# FP6120.net
KiCad netlist of a schematic drawn in EAGLE
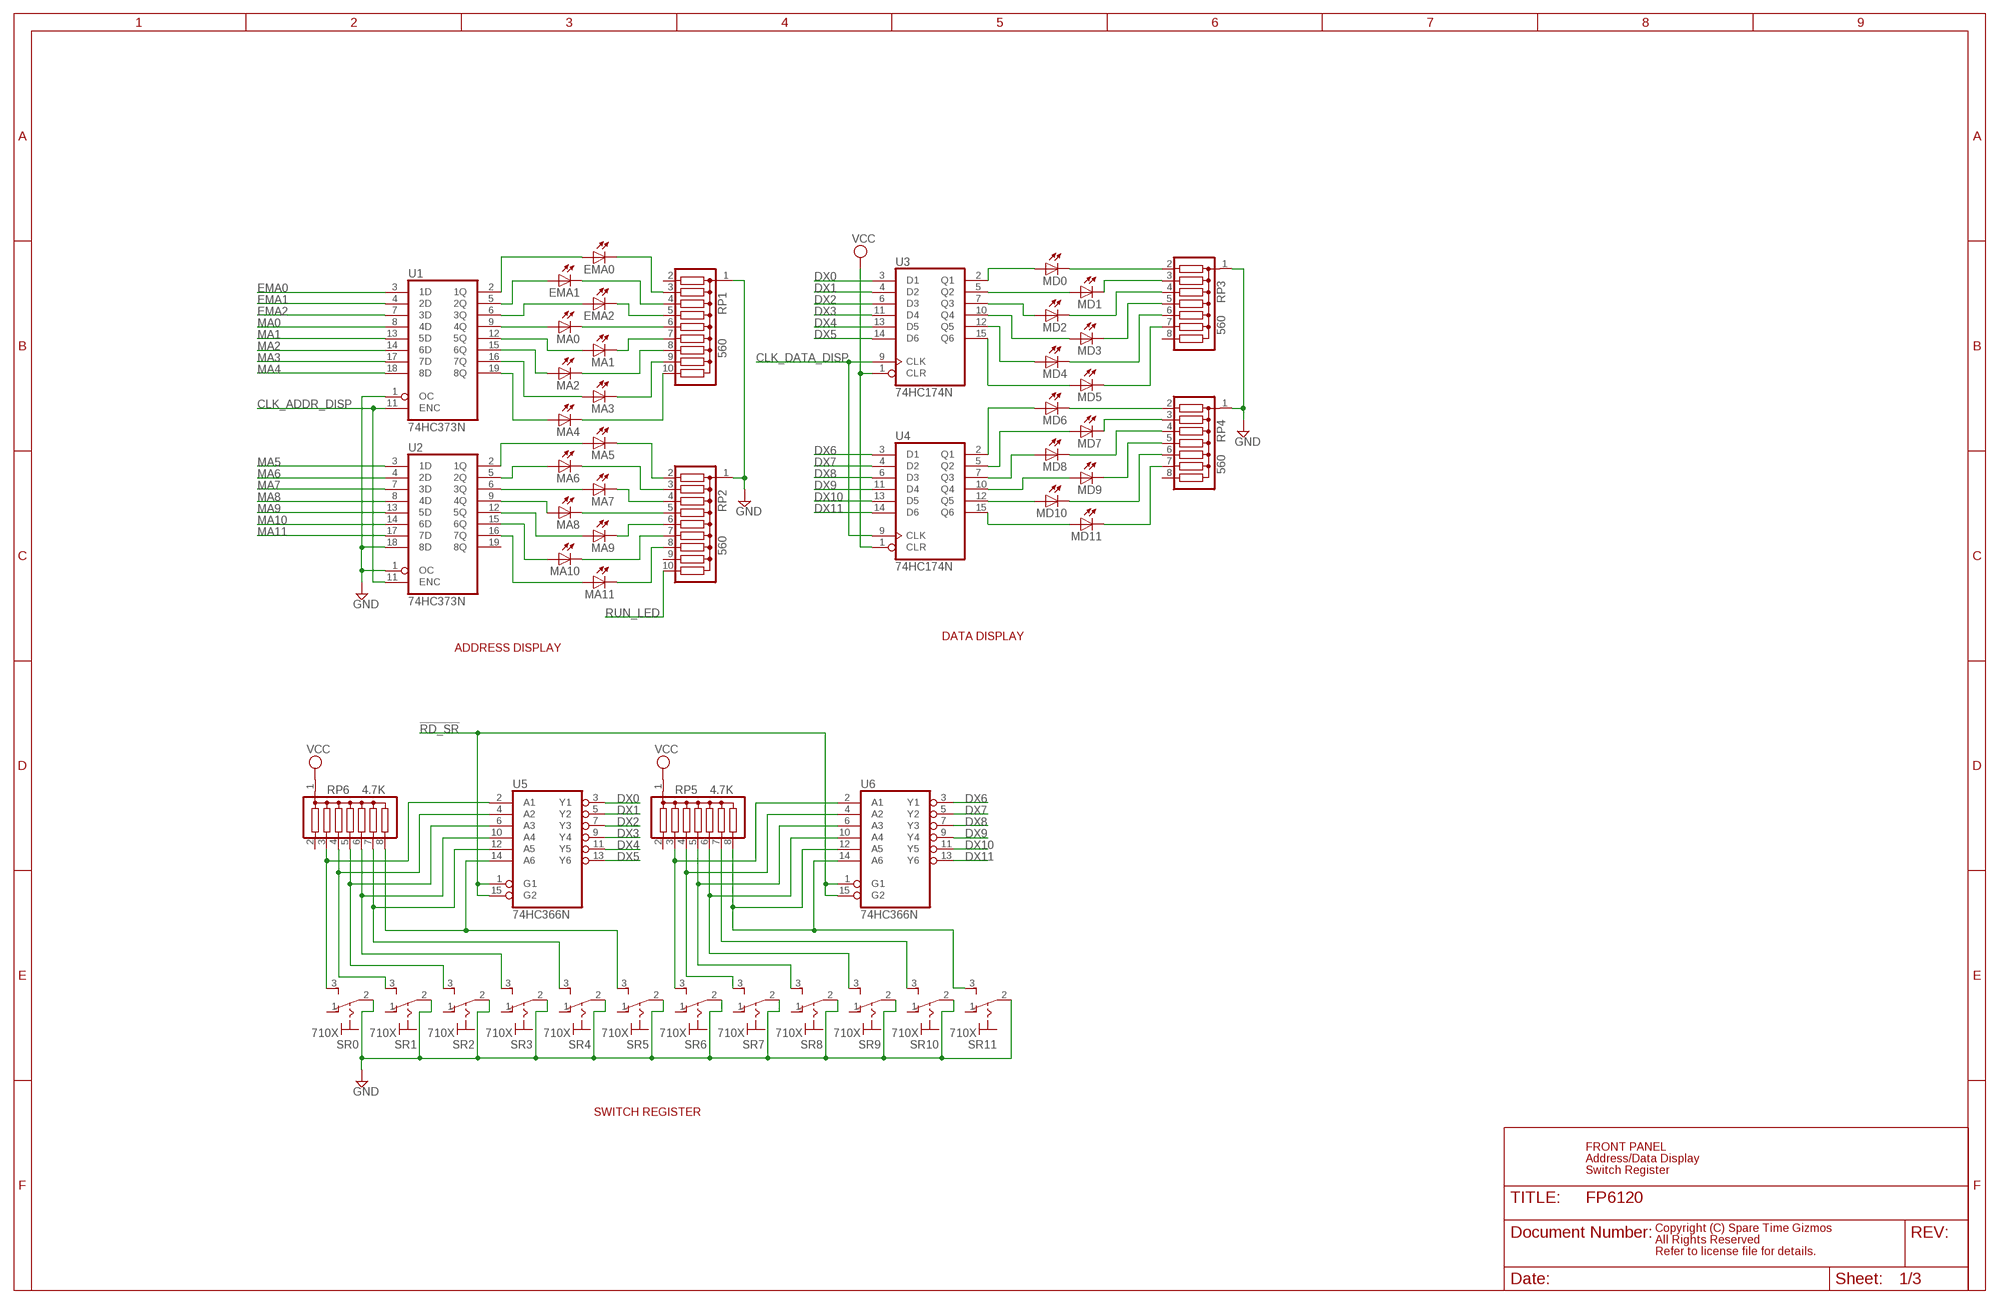
[diagram p0: schematic, sheet 1]
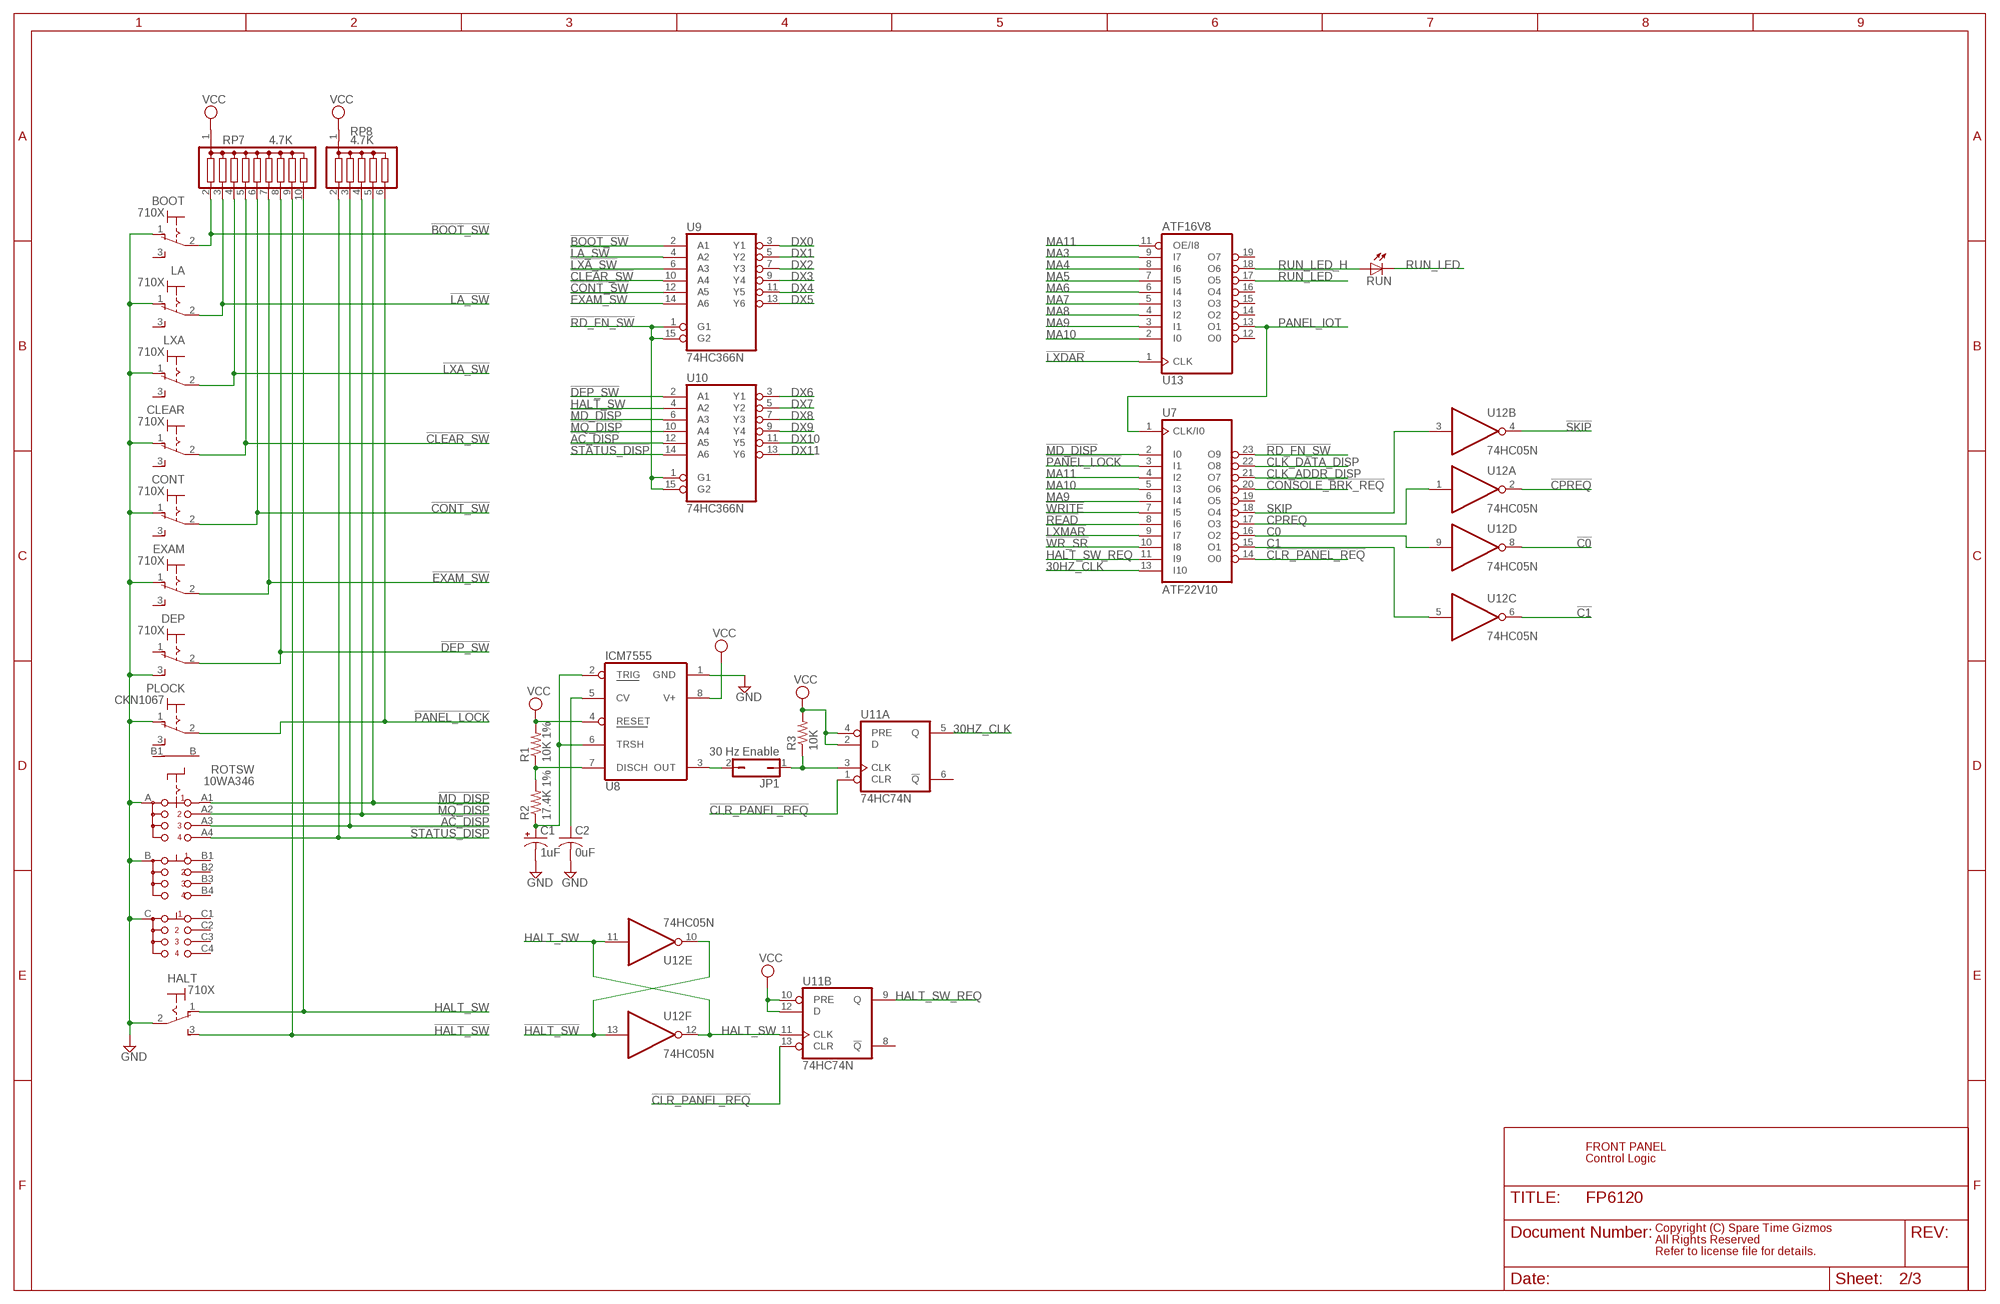
[diagram p1: schematic, sheet 2]
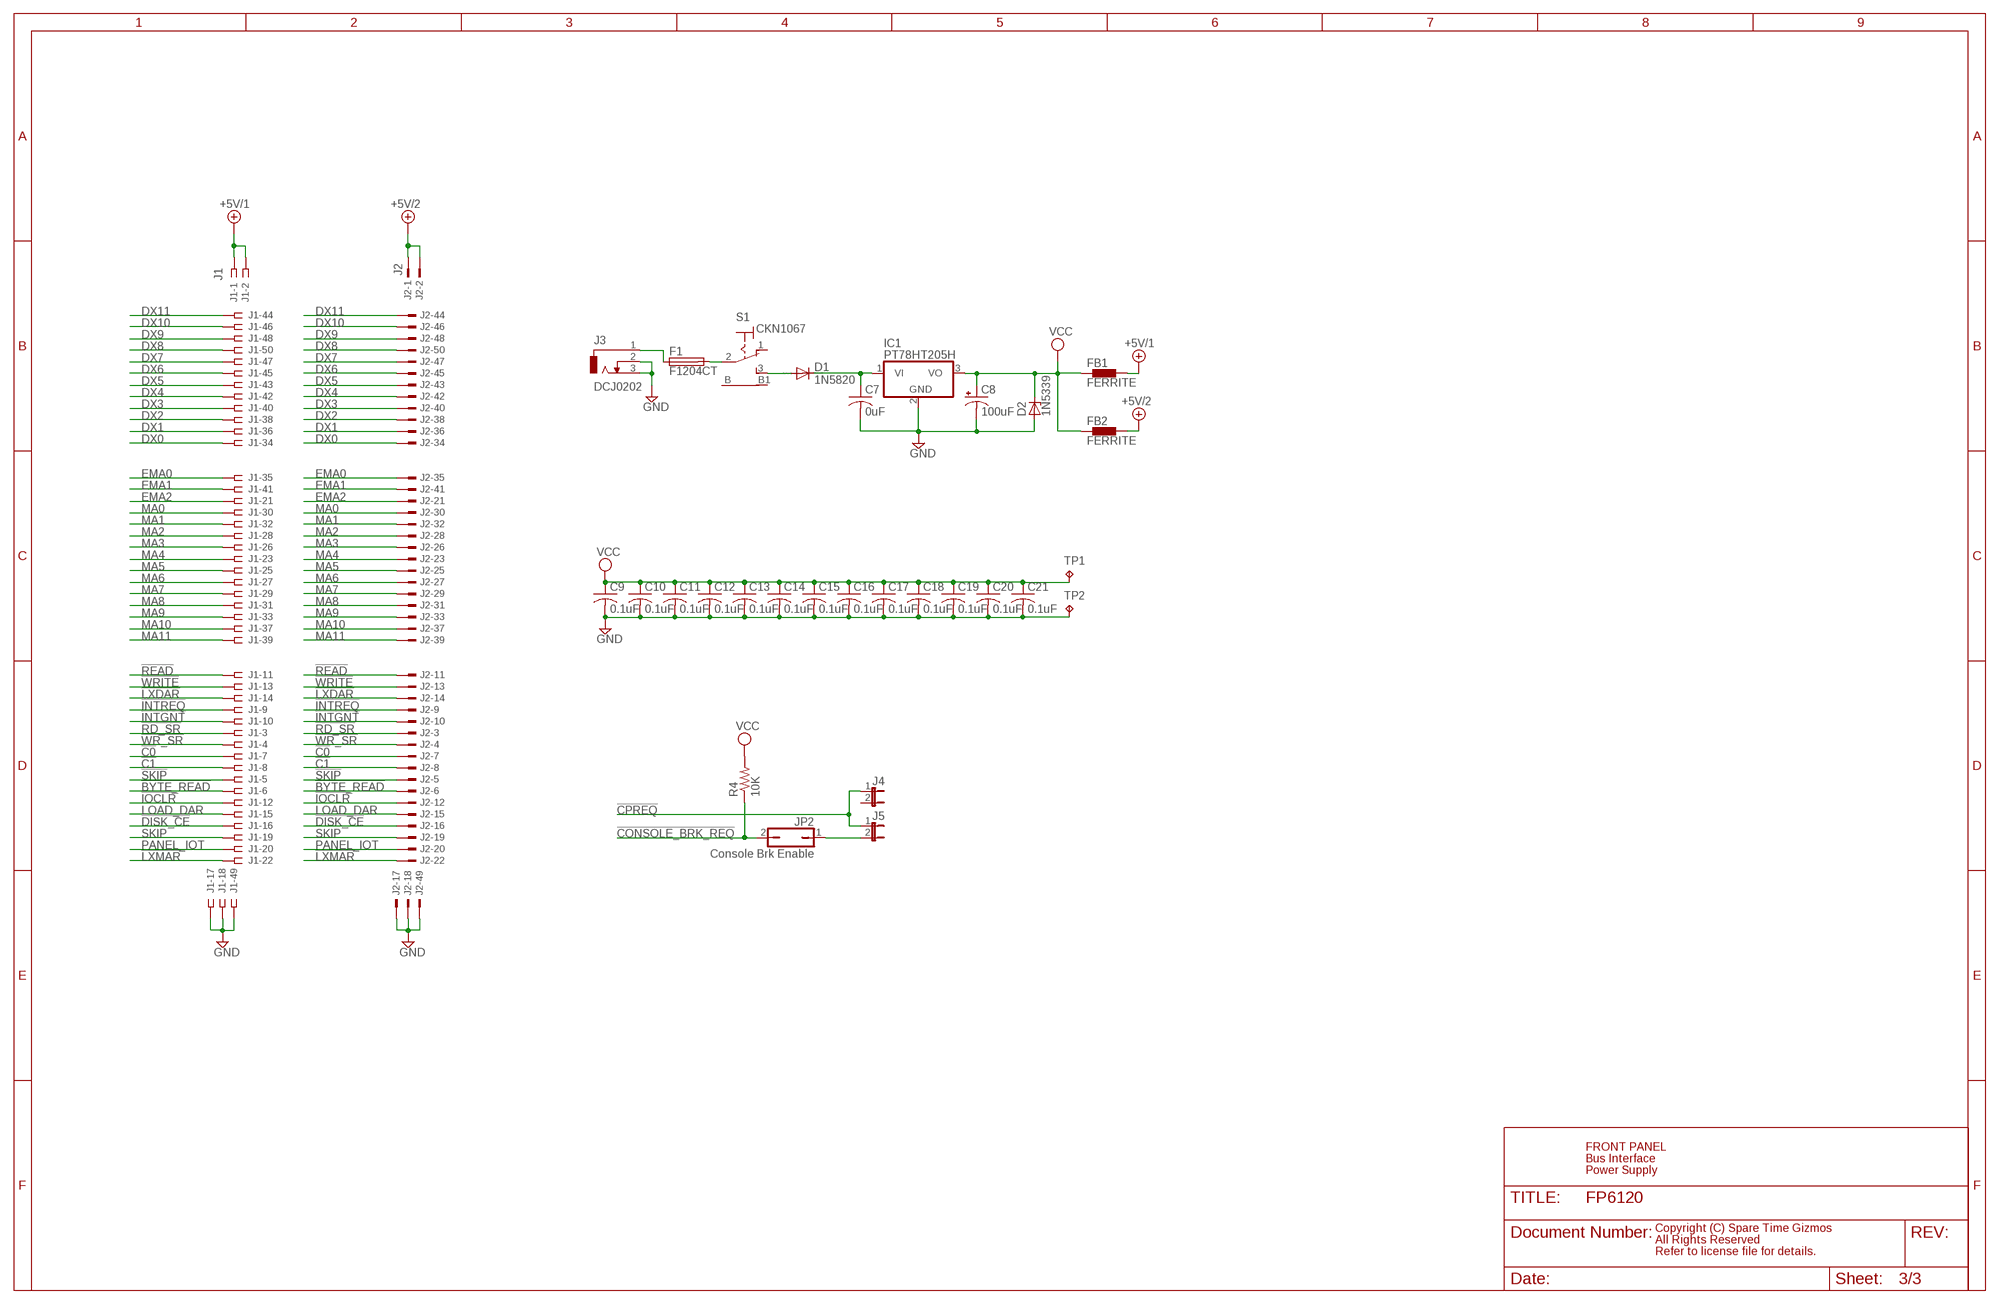
[diagram p2: schematic, sheet 3]

(export (version "E")
  (design (tool "Eeschema 10.0.6"))
  (components
    (comp (ref "BOOT")
      (value "710X")
      (footprint "eagle-import:7109MD9V3")
      (libsource (lib "eagle-import") (part "710X"))
    )
    (comp (ref "C1")
      (value "1uF")
      (footprint "eagle-import:B45181A")
      (libsource (lib "eagle-import") (part "CPOL-USB45181A"))
    )
    (comp (ref "C2")
      (value "0uF")
      (footprint "eagle-import:C050-024X044")
      (libsource (lib "eagle-import") (part "C-US050-024X044"))
    )
    (comp (ref "CLEAR")
      (value "710X")
      (footprint "eagle-import:7109MD9V3")
      (libsource (lib "eagle-import") (part "710X"))
    )
    (comp (ref "CONT")
      (value "710X")
      (footprint "eagle-import:7109MD9V3")
      (libsource (lib "eagle-import") (part "710X"))
    )
    (comp (ref "DEP")
      (value "710X")
      (footprint "eagle-import:7109MD9V3")
      (libsource (lib "eagle-import") (part "710X"))
    )
    (comp (ref "EXAM")
      (value "710X")
      (footprint "eagle-import:7109MD9V3")
      (libsource (lib "eagle-import") (part "710X"))
    )
    (comp (ref "HALT")
      (value "710X")
      (footprint "eagle-import:7109MD9V3")
      (libsource (lib "eagle-import") (part "710X"))
    )
    (comp (ref "JP1")
      (value "30 Hz Enable")
      (footprint "eagle-import:JP1")
      (libsource (lib "eagle-import") (part "JP1Q"))
    )
    (comp (ref "LA")
      (value "710X")
      (footprint "eagle-import:7109MD9V3")
      (libsource (lib "eagle-import") (part "710X"))
    )
    (comp (ref "LXA")
      (value "710X")
      (footprint "eagle-import:7109MD9V3")
      (libsource (lib "eagle-import") (part "710X"))
    )
    (comp (ref "PLOCK")
      (value "CKN1067")
      (footprint "eagle-import:9070-1W")
      (libsource (lib "eagle-import") (part "9070-1W"))
    )
    (comp (ref "R1")
      (value "10K 1%")
      (footprint "eagle-import:0204_7")
      (libsource (lib "eagle-import") (part "R-US_0204/7"))
    )
    (comp (ref "R2")
      (value "17.4K 1%")
      (footprint "eagle-import:0204_7")
      (libsource (lib "eagle-import") (part "R-US_0204/7"))
    )
    (comp (ref "R3")
      (value "10K")
      (footprint "eagle-import:0204_7")
      (libsource (lib "eagle-import") (part "R-US_0204/7"))
    )
    (comp (ref "ROTSW")
      (value "10WA346")
      (footprint "eagle-import:CK103X04")
      (libsource (lib "eagle-import") (part "CK103X04"))
    )
    (comp (ref "RP7")
      (value "4.7K")
      (footprint "eagle-import:SIL10")
      (libsource (lib "eagle-import") (part "G09R"))
    )
    (comp (ref "RP8")
      (value "4.7K")
      (footprint "eagle-import:SIL6")
      (libsource (lib "eagle-import") (part "G05R"))
    )
    (comp (ref "RUN")
      (value "LED5MM")
      (footprint "eagle-import:LED5MM")
      (libsource (lib "eagle-import") (part "LED5MM"))
    )
    (comp (ref "U7")
      (value "ATF22V10")
      (footprint "eagle-import:DIL24-3")
      (fields (field (name "MPN") "GAL22V10D-7LPN"))
      (libsource (lib "eagle-import") (part "22V10"))
    )
    (comp (ref "U8")
      (value "ICM7555")
      (footprint "eagle-import:DIL08")
      (fields (field (name "MF") "MAXIM") (field (name "MPN") "ICM7555IPA+"))
      (libsource (lib "eagle-import") (part "ICM7555"))
    )
    (comp (ref "U9")
      (value "74HC366N")
      (footprint "eagle-import:DIL16")
      (libsource (lib "eagle-import") (part "74366NLS"))
    )
    (comp (ref "U10")
      (value "74HC366N")
      (footprint "eagle-import:DIL16")
      (libsource (lib "eagle-import") (part "74366NLS"))
    )
    (comp (ref "U11")
      (value "74HC74N")
      (footprint "eagle-import:DIL14")
      (libsource (lib "eagle-import") (part "7474NLS"))
    )
    (comp (ref "U12")
      (value "74HC05N")
      (footprint "eagle-import:DIL14")
      (libsource (lib "eagle-import") (part "7405NLS"))
    )
    (comp (ref "U13")
      (value "ATF16V8")
      (footprint "eagle-import:DIL20")
      (fields (field (name "MPN") "GAL16V8D-7LPN"))
      (libsource (lib "eagle-import") (part "16V8"))
    )
    (comp (ref "EMA0")
      (value "LED5MM")
      (footprint "eagle-import:LED5MM")
      (libsource (lib "eagle-import") (part "LED5MM"))
    )
    (comp (ref "EMA1")
      (value "LED5MM")
      (footprint "eagle-import:LED5MM")
      (libsource (lib "eagle-import") (part "LED5MM"))
    )
    (comp (ref "EMA2")
      (value "LED5MM")
      (footprint "eagle-import:LED5MM")
      (libsource (lib "eagle-import") (part "LED5MM"))
    )
    (comp (ref "MA0")
      (value "LED5MM")
      (footprint "eagle-import:LED5MM")
      (libsource (lib "eagle-import") (part "LED5MM"))
    )
    (comp (ref "MA1")
      (value "LED5MM")
      (footprint "eagle-import:LED5MM")
      (libsource (lib "eagle-import") (part "LED5MM"))
    )
    (comp (ref "MA2")
      (value "LED5MM")
      (footprint "eagle-import:LED5MM")
      (libsource (lib "eagle-import") (part "LED5MM"))
    )
    (comp (ref "MA3")
      (value "LED5MM")
      (footprint "eagle-import:LED5MM")
      (libsource (lib "eagle-import") (part "LED5MM"))
    )
    (comp (ref "MA4")
      (value "LED5MM")
      (footprint "eagle-import:LED5MM")
      (libsource (lib "eagle-import") (part "LED5MM"))
    )
    (comp (ref "MA5")
      (value "LED5MM")
      (footprint "eagle-import:LED5MM")
      (libsource (lib "eagle-import") (part "LED5MM"))
    )
    (comp (ref "MA6")
      (value "LED5MM")
      (footprint "eagle-import:LED5MM")
      (libsource (lib "eagle-import") (part "LED5MM"))
    )
    (comp (ref "MA7")
      (value "LED5MM")
      (footprint "eagle-import:LED5MM")
      (libsource (lib "eagle-import") (part "LED5MM"))
    )
    (comp (ref "MA8")
      (value "LED5MM")
      (footprint "eagle-import:LED5MM")
      (libsource (lib "eagle-import") (part "LED5MM"))
    )
    (comp (ref "MA9")
      (value "LED5MM")
      (footprint "eagle-import:LED5MM")
      (libsource (lib "eagle-import") (part "LED5MM"))
    )
    (comp (ref "MA10")
      (value "LED5MM")
      (footprint "eagle-import:LED5MM")
      (libsource (lib "eagle-import") (part "LED5MM"))
    )
    (comp (ref "MA11")
      (value "LED5MM")
      (footprint "eagle-import:LED5MM")
      (libsource (lib "eagle-import") (part "LED5MM"))
    )
    (comp (ref "MD0")
      (value "LED5MM")
      (footprint "eagle-import:LED5MM")
      (libsource (lib "eagle-import") (part "LED5MM"))
    )
    (comp (ref "MD1")
      (value "LED5MM")
      (footprint "eagle-import:LED5MM")
      (libsource (lib "eagle-import") (part "LED5MM"))
    )
    (comp (ref "MD2")
      (value "LED5MM")
      (footprint "eagle-import:LED5MM")
      (libsource (lib "eagle-import") (part "LED5MM"))
    )
    (comp (ref "MD3")
      (value "LED5MM")
      (footprint "eagle-import:LED5MM")
      (libsource (lib "eagle-import") (part "LED5MM"))
    )
    (comp (ref "MD4")
      (value "LED5MM")
      (footprint "eagle-import:LED5MM")
      (libsource (lib "eagle-import") (part "LED5MM"))
    )
    (comp (ref "MD5")
      (value "LED5MM")
      (footprint "eagle-import:LED5MM")
      (libsource (lib "eagle-import") (part "LED5MM"))
    )
    (comp (ref "MD6")
      (value "LED5MM")
      (footprint "eagle-import:LED5MM")
      (libsource (lib "eagle-import") (part "LED5MM"))
    )
    (comp (ref "MD7")
      (value "LED5MM")
      (footprint "eagle-import:LED5MM")
      (libsource (lib "eagle-import") (part "LED5MM"))
    )
    (comp (ref "MD8")
      (value "LED5MM")
      (footprint "eagle-import:LED5MM")
      (libsource (lib "eagle-import") (part "LED5MM"))
    )
    (comp (ref "MD9")
      (value "LED5MM")
      (footprint "eagle-import:LED5MM")
      (libsource (lib "eagle-import") (part "LED5MM"))
    )
    (comp (ref "MD10")
      (value "LED5MM")
      (footprint "eagle-import:LED5MM")
      (libsource (lib "eagle-import") (part "LED5MM"))
    )
    (comp (ref "MD11")
      (value "LED5MM")
      (footprint "eagle-import:LED5MM")
      (libsource (lib "eagle-import") (part "LED5MM"))
    )
    (comp (ref "RP1")
      (value "560")
      (footprint "eagle-import:SIL10")
      (libsource (lib "eagle-import") (part "G09R"))
    )
    (comp (ref "RP2")
      (value "560")
      (footprint "eagle-import:SIL10")
      (libsource (lib "eagle-import") (part "G09R"))
    )
    (comp (ref "RP3")
      (value "560")
      (footprint "eagle-import:SIL8")
      (libsource (lib "eagle-import") (part "G07R"))
    )
    (comp (ref "RP4")
      (value "560")
      (footprint "eagle-import:SIL8")
      (libsource (lib "eagle-import") (part "G07R"))
    )
    (comp (ref "RP5")
      (value "4.7K")
      (footprint "eagle-import:SIL8")
      (libsource (lib "eagle-import") (part "G07R"))
    )
    (comp (ref "RP6")
      (value "4.7K")
      (footprint "eagle-import:SIL8")
      (libsource (lib "eagle-import") (part "G07R"))
    )
    (comp (ref "SR0")
      (value "710X")
      (footprint "eagle-import:7109MD9V3")
      (libsource (lib "eagle-import") (part "710X"))
    )
    (comp (ref "SR1")
      (value "710X")
      (footprint "eagle-import:7109MD9V3")
      (libsource (lib "eagle-import") (part "710X"))
    )
    (comp (ref "SR2")
      (value "710X")
      (footprint "eagle-import:7109MD9V3")
      (libsource (lib "eagle-import") (part "710X"))
    )
    (comp (ref "SR3")
      (value "710X")
      (footprint "eagle-import:7109MD9V3")
      (libsource (lib "eagle-import") (part "710X"))
    )
    (comp (ref "SR4")
      (value "710X")
      (footprint "eagle-import:7109MD9V3")
      (libsource (lib "eagle-import") (part "710X"))
    )
    (comp (ref "SR5")
      (value "710X")
      (footprint "eagle-import:7109MD9V3")
      (libsource (lib "eagle-import") (part "710X"))
    )
    (comp (ref "SR6")
      (value "710X")
      (footprint "eagle-import:7109MD9V3")
      (libsource (lib "eagle-import") (part "710X"))
    )
    (comp (ref "SR7")
      (value "710X")
      (footprint "eagle-import:7109MD9V3")
      (libsource (lib "eagle-import") (part "710X"))
    )
    (comp (ref "SR8")
      (value "710X")
      (footprint "eagle-import:7109MD9V3")
      (libsource (lib "eagle-import") (part "710X"))
    )
    (comp (ref "SR9")
      (value "710X")
      (footprint "eagle-import:7109MD9V3")
      (libsource (lib "eagle-import") (part "710X"))
    )
    (comp (ref "SR10")
      (value "710X")
      (footprint "eagle-import:7109MD9V3")
      (libsource (lib "eagle-import") (part "710X"))
    )
    (comp (ref "SR11")
      (value "710X")
      (footprint "eagle-import:7109MD9V3")
      (libsource (lib "eagle-import") (part "710X"))
    )
    (comp (ref "U1")
      (value "74HC373N")
      (footprint "eagle-import:DIL20")
      (libsource (lib "eagle-import") (part "74373NLS"))
    )
    (comp (ref "U2")
      (value "74HC373N")
      (footprint "eagle-import:DIL20")
      (libsource (lib "eagle-import") (part "74373NLS"))
    )
    (comp (ref "U3")
      (value "74HC174N")
      (footprint "eagle-import:DIL16")
      (libsource (lib "eagle-import") (part "74174NLS"))
    )
    (comp (ref "U4")
      (value "74HC174N")
      (footprint "eagle-import:DIL16")
      (libsource (lib "eagle-import") (part "74174NLS"))
    )
    (comp (ref "U5")
      (value "74HC366N")
      (footprint "eagle-import:DIL16")
      (libsource (lib "eagle-import") (part "74366NLS"))
    )
    (comp (ref "U6")
      (value "74HC366N")
      (footprint "eagle-import:DIL16")
      (libsource (lib "eagle-import") (part "74366NLS"))
    )
    (comp (ref "C7")
      (value "0uF")
      (footprint "eagle-import:C050-024X044")
      (libsource (lib "eagle-import") (part "C-US050-024X044"))
    )
    (comp (ref "C8")
      (value "100uF")
      (footprint "eagle-import:B45181A")
      (libsource (lib "eagle-import") (part "CPOL-USB45181A"))
    )
    (comp (ref "C9")
      (value "0.1uF")
      (footprint "eagle-import:C025-025X050")
      (libsource (lib "eagle-import") (part "C-US025-025X050"))
    )
    (comp (ref "C10")
      (value "0.1uF")
      (footprint "eagle-import:C025-025X050")
      (libsource (lib "eagle-import") (part "C-US025-025X050"))
    )
    (comp (ref "C11")
      (value "0.1uF")
      (footprint "eagle-import:C025-025X050")
      (libsource (lib "eagle-import") (part "C-US025-025X050"))
    )
    (comp (ref "C12")
      (value "0.1uF")
      (footprint "eagle-import:C025-025X050")
      (libsource (lib "eagle-import") (part "C-US025-025X050"))
    )
    (comp (ref "C13")
      (value "0.1uF")
      (footprint "eagle-import:C025-025X050")
      (libsource (lib "eagle-import") (part "C-US025-025X050"))
    )
    (comp (ref "C14")
      (value "0.1uF")
      (footprint "eagle-import:C025-025X050")
      (libsource (lib "eagle-import") (part "C-US025-025X050"))
    )
    (comp (ref "C15")
      (value "0.1uF")
      (footprint "eagle-import:C025-025X050")
      (libsource (lib "eagle-import") (part "C-US025-025X050"))
    )
    (comp (ref "C16")
      (value "0.1uF")
      (footprint "eagle-import:C025-025X050")
      (libsource (lib "eagle-import") (part "C-US025-025X050"))
    )
    (comp (ref "C17")
      (value "0.1uF")
      (footprint "eagle-import:C025-025X050")
      (libsource (lib "eagle-import") (part "C-US025-025X050"))
    )
    (comp (ref "C18")
      (value "0.1uF")
      (footprint "eagle-import:C025-025X050")
      (libsource (lib "eagle-import") (part "C-US025-025X050"))
    )
    (comp (ref "C19")
      (value "0.1uF")
      (footprint "eagle-import:C025-025X050")
      (libsource (lib "eagle-import") (part "C-US025-025X050"))
    )
    (comp (ref "C20")
      (value "0.1uF")
      (footprint "eagle-import:C025-025X050")
      (libsource (lib "eagle-import") (part "C-US025-025X050"))
    )
    (comp (ref "C21")
      (value "0.1uF")
      (footprint "eagle-import:C025-025X050")
      (libsource (lib "eagle-import") (part "C-US025-025X050"))
    )
    (comp (ref "D1")
      (value "1N5820")
      (footprint "eagle-import:SOD61B")
      (libsource (lib "eagle-import") (part "DIODE-SOD61B"))
    )
    (comp (ref "D2")
      (value "1N5339")
      (footprint "eagle-import:ZDIO12.5")
      (libsource (lib "eagle-import") (part "ZENER-DIODEZD-12.5"))
    )
    (comp (ref "F1")
      (value "F1204CT")
      (footprint "eagle-import:PICOFUSE")
      (libsource (lib "eagle-import") (part "PICOFUSE"))
    )
    (comp (ref "FB1")
      (value "FERRITE")
      (footprint "eagle-import:BL01RN1A")
      (libsource (lib "eagle-import") (part "BL01RN1A"))
    )
    (comp (ref "FB2")
      (value "FERRITE")
      (footprint "eagle-import:BL01RN1A")
      (libsource (lib "eagle-import") (part "BL01RN1A"))
    )
    (comp (ref "IC1")
      (value "PT78HT205H")
      (footprint "eagle-import:TO220H")
      (libsource (lib "eagle-import") (part "78T05"))
    )
    (comp (ref "J1")
      (value "J1")
      (footprint "eagle-import:SSW-125-02-S-D")
      (fields (field (name "MPN") "SSW-125-02-S-D"))
      (libsource (lib "eagle-import") (part "SSW-125-02-S-D"))
    )
    (comp (ref "J2")
      (value "J2")
      (footprint "eagle-import:TSW-125-02-S-D")
      (libsource (lib "eagle-import") (part "TSW-125-02-S-D"))
    )
    (comp (ref "J3")
      (value "DCJ0202")
      (footprint "eagle-import:DCJ0202")
      (libsource (lib "eagle-import") (part "DCJ0202"))
    )
    (comp (ref "J4")
      (value "JP1E")
      (footprint "eagle-import:JP1")
      (libsource (lib "eagle-import") (part "JP1E"))
    )
    (comp (ref "J5")
      (value "JP1E")
      (footprint "eagle-import:JP1")
      (libsource (lib "eagle-import") (part "JP1E"))
    )
    (comp (ref "JP2")
      (value "Console Brk Enable")
      (footprint "eagle-import:JP1")
      (libsource (lib "eagle-import") (part "JP1Q"))
    )
    (comp (ref "R4")
      (value "10K")
      (footprint "eagle-import:0204_7")
      (libsource (lib "eagle-import") (part "R-US_0204/7"))
    )
    (comp (ref "S1")
      (value "CKN1067")
      (footprint "eagle-import:9070-1W")
      (libsource (lib "eagle-import") (part "9070-1W"))
    )
    (comp (ref "TP1")
      (value "TPPAD1-20Y")
      (footprint "eagle-import:P1-20Y")
      (libsource (lib "eagle-import") (part "TPPAD1-20Y"))
    )
    (comp (ref "TP2")
      (value "TPPAD1-20Y")
      (footprint "eagle-import:P1-20Y")
      (libsource (lib "eagle-import") (part "TPPAD1-20Y"))
    )
  )
  (nets
    (net (code "1") (name "+5V{slash}1") (class "Default")
      (node (ref "FB1") (pin "2") (pinfunction "2_2") (pintype "passive"))
      (node (ref "J1") (pin "1") (pinfunction "1_1") (pintype "passive"))
      (node (ref "J1") (pin "2") (pinfunction "1_2") (pintype "passive"))
    )
    (net (code "2") (name "+5V{slash}2") (class "Default")
      (node (ref "FB2") (pin "2") (pinfunction "2_2") (pintype "passive"))
      (node (ref "J2") (pin "1") (pinfunction "1_1") (pintype "passive"))
      (node (ref "J2") (pin "2") (pinfunction "1_2") (pintype "passive"))
    )
    (net (code "3") (name "30HZ_CLK") (class "Default")
      (node (ref "U11") (pin "5") (pinfunction "Q_5") (pintype "output"))
      (node (ref "U7") (pin "13") (pinfunction "I10_13") (pintype "input"))
    )
    (net (code "4") (name "C0") (class "Default")
      (node (ref "U12") (pin "9") (pinfunction "I_9") (pintype "input"))
      (node (ref "U7") (pin "16") (pinfunction "O2_16") (pintype "bidirectional"))
    )
    (net (code "5") (name "C1") (class "Default")
      (node (ref "U12") (pin "5") (pinfunction "I_5") (pintype "input"))
      (node (ref "U7") (pin "15") (pinfunction "O1_15") (pintype "bidirectional"))
    )
    (net (code "6") (name "CLK_ADDR_DISP") (class "Default")
      (node (ref "U1") (pin "11") (pinfunction "ENC_11") (pintype "input"))
      (node (ref "U2") (pin "11") (pinfunction "ENC_11") (pintype "input"))
      (node (ref "U7") (pin "21") (pinfunction "O7_21") (pintype "bidirectional"))
    )
    (net (code "7") (name "CLK_DATA_DISP") (class "Default")
      (node (ref "U3") (pin "9") (pinfunction "CLK_9") (pintype "input"))
      (node (ref "U4") (pin "9") (pinfunction "CLK_9") (pintype "input"))
      (node (ref "U7") (pin "22") (pinfunction "O8_22") (pintype "bidirectional"))
    )
    (net (code "8") (name "CPREQ") (class "Default")
      (node (ref "U12") (pin "1") (pinfunction "I_1") (pintype "input"))
      (node (ref "U7") (pin "17") (pinfunction "O3_17") (pintype "bidirectional"))
    )
    (net (code "9") (name "DX0") (class "Default")
      (node (ref "J1") (pin "34") (pinfunction "1_34") (pintype "passive"))
      (node (ref "J2") (pin "34") (pinfunction "1_34") (pintype "passive"))
      (node (ref "U3") (pin "3") (pinfunction "D1_3") (pintype "input"))
      (node (ref "U5") (pin "3") (pinfunction "Y1_3") (pintype "tri_state"))
      (node (ref "U9") (pin "3") (pinfunction "Y1_3") (pintype "tri_state"))
    )
    (net (code "10") (name "DX1") (class "Default")
      (node (ref "J1") (pin "36") (pinfunction "1_36") (pintype "passive"))
      (node (ref "J2") (pin "36") (pinfunction "1_36") (pintype "passive"))
      (node (ref "U3") (pin "4") (pinfunction "D2_4") (pintype "input"))
      (node (ref "U5") (pin "5") (pinfunction "Y2_5") (pintype "tri_state"))
      (node (ref "U9") (pin "5") (pinfunction "Y2_5") (pintype "tri_state"))
    )
    (net (code "11") (name "DX2") (class "Default")
      (node (ref "J1") (pin "38") (pinfunction "1_38") (pintype "passive"))
      (node (ref "J2") (pin "38") (pinfunction "1_38") (pintype "passive"))
      (node (ref "U3") (pin "6") (pinfunction "D3_6") (pintype "input"))
      (node (ref "U5") (pin "7") (pinfunction "Y3_7") (pintype "tri_state"))
      (node (ref "U9") (pin "7") (pinfunction "Y3_7") (pintype "tri_state"))
    )
    (net (code "12") (name "DX3") (class "Default")
      (node (ref "J1") (pin "40") (pinfunction "1_40") (pintype "passive"))
      (node (ref "J2") (pin "40") (pinfunction "1_40") (pintype "passive"))
      (node (ref "U3") (pin "11") (pinfunction "D4_11") (pintype "input"))
      (node (ref "U5") (pin "9") (pinfunction "Y4_9") (pintype "tri_state"))
      (node (ref "U9") (pin "9") (pinfunction "Y4_9") (pintype "tri_state"))
    )
    (net (code "13") (name "DX4") (class "Default")
      (node (ref "J1") (pin "42") (pinfunction "1_42") (pintype "passive"))
      (node (ref "J2") (pin "42") (pinfunction "1_42") (pintype "passive"))
      (node (ref "U3") (pin "13") (pinfunction "D5_13") (pintype "input"))
      (node (ref "U5") (pin "11") (pinfunction "Y5_11") (pintype "tri_state"))
      (node (ref "U9") (pin "11") (pinfunction "Y5_11") (pintype "tri_state"))
    )
    (net (code "14") (name "DX5") (class "Default")
      (node (ref "J1") (pin "43") (pinfunction "1_43") (pintype "passive"))
      (node (ref "J2") (pin "43") (pinfunction "1_43") (pintype "passive"))
      (node (ref "U3") (pin "14") (pinfunction "D6_14") (pintype "input"))
      (node (ref "U5") (pin "13") (pinfunction "Y6_13") (pintype "tri_state"))
      (node (ref "U9") (pin "13") (pinfunction "Y6_13") (pintype "tri_state"))
    )
    (net (code "15") (name "DX6") (class "Default")
      (node (ref "J1") (pin "45") (pinfunction "1_45") (pintype "passive"))
      (node (ref "J2") (pin "45") (pinfunction "1_45") (pintype "passive"))
      (node (ref "U10") (pin "3") (pinfunction "Y1_3") (pintype "tri_state"))
      (node (ref "U4") (pin "3") (pinfunction "D1_3") (pintype "input"))
      (node (ref "U6") (pin "3") (pinfunction "Y1_3") (pintype "tri_state"))
    )
    (net (code "16") (name "DX7") (class "Default")
      (node (ref "J1") (pin "47") (pinfunction "1_47") (pintype "passive"))
      (node (ref "J2") (pin "47") (pinfunction "1_47") (pintype "passive"))
      (node (ref "U10") (pin "5") (pinfunction "Y2_5") (pintype "tri_state"))
      (node (ref "U4") (pin "4") (pinfunction "D2_4") (pintype "input"))
      (node (ref "U6") (pin "5") (pinfunction "Y2_5") (pintype "tri_state"))
    )
    (net (code "17") (name "DX8") (class "Default")
      (node (ref "J1") (pin "50") (pinfunction "1_50") (pintype "passive"))
      (node (ref "J2") (pin "50") (pinfunction "1_50") (pintype "passive"))
      (node (ref "U10") (pin "7") (pinfunction "Y3_7") (pintype "tri_state"))
      (node (ref "U4") (pin "6") (pinfunction "D3_6") (pintype "input"))
      (node (ref "U6") (pin "7") (pinfunction "Y3_7") (pintype "tri_state"))
    )
    (net (code "18") (name "DX9") (class "Default")
      (node (ref "J1") (pin "48") (pinfunction "1_48") (pintype "passive"))
      (node (ref "J2") (pin "48") (pinfunction "1_48") (pintype "passive"))
      (node (ref "U10") (pin "9") (pinfunction "Y4_9") (pintype "tri_state"))
      (node (ref "U4") (pin "11") (pinfunction "D4_11") (pintype "input"))
      (node (ref "U6") (pin "9") (pinfunction "Y4_9") (pintype "tri_state"))
    )
    (net (code "19") (name "DX10") (class "Default")
      (node (ref "J1") (pin "46") (pinfunction "1_46") (pintype "passive"))
      (node (ref "J2") (pin "46") (pinfunction "1_46") (pintype "passive"))
      (node (ref "U10") (pin "11") (pinfunction "Y5_11") (pintype "tri_state"))
      (node (ref "U4") (pin "13") (pinfunction "D5_13") (pintype "input"))
      (node (ref "U6") (pin "11") (pinfunction "Y5_11") (pintype "tri_state"))
    )
    (net (code "20") (name "DX11") (class "Default")
      (node (ref "J1") (pin "44") (pinfunction "1_44") (pintype "passive"))
      (node (ref "J2") (pin "44") (pinfunction "1_44") (pintype "passive"))
      (node (ref "U10") (pin "13") (pinfunction "Y6_13") (pintype "tri_state"))
      (node (ref "U4") (pin "14") (pinfunction "D6_14") (pintype "input"))
      (node (ref "U6") (pin "13") (pinfunction "Y6_13") (pintype "tri_state"))
    )
    (net (code "21") (name "EMA0") (class "Default")
      (node (ref "J1") (pin "35") (pinfunction "1_35") (pintype "passive"))
      (node (ref "J2") (pin "35") (pinfunction "1_35") (pintype "passive"))
      (node (ref "U1") (pin "3") (pinfunction "1D_3") (pintype "input"))
    )
    (net (code "22") (name "EMA1") (class "Default")
      (node (ref "J1") (pin "41") (pinfunction "1_41") (pintype "passive"))
      (node (ref "J2") (pin "41") (pinfunction "1_41") (pintype "passive"))
      (node (ref "U1") (pin "4") (pinfunction "2D_4") (pintype "input"))
    )
    (net (code "23") (name "EMA2") (class "Default")
      (node (ref "J1") (pin "21") (pinfunction "1_21") (pintype "passive"))
      (node (ref "J2") (pin "21") (pinfunction "1_21") (pintype "passive"))
      (node (ref "U1") (pin "7") (pinfunction "3D_7") (pintype "input"))
    )
    (net (code "24") (name "GND") (class "Default")
      (node (ref "BOOT") (pin "1") (pinfunction "O_1") (pintype "passive"))
      (node (ref "C1") (pin "-") (pinfunction "-_-") (pintype "passive"))
      (node (ref "C10") (pin "2") (pinfunction "2_2") (pintype "passive"))
      (node (ref "C11") (pin "2") (pinfunction "2_2") (pintype "passive"))
      (node (ref "C12") (pin "2") (pinfunction "2_2") (pintype "passive"))
      (node (ref "C13") (pin "2") (pinfunction "2_2") (pintype "passive"))
      (node (ref "C14") (pin "2") (pinfunction "2_2") (pintype "passive"))
      (node (ref "C15") (pin "2") (pinfunction "2_2") (pintype "passive"))
      (node (ref "C16") (pin "2") (pinfunction "2_2") (pintype "passive"))
      (node (ref "C17") (pin "2") (pinfunction "2_2") (pintype "passive"))
      (node (ref "C18") (pin "2") (pinfunction "2_2") (pintype "passive"))
      (node (ref "C19") (pin "2") (pinfunction "2_2") (pintype "passive"))
      (node (ref "C2") (pin "2") (pinfunction "2_2") (pintype "passive"))
      (node (ref "C20") (pin "2") (pinfunction "2_2") (pintype "passive"))
      (node (ref "C21") (pin "2") (pinfunction "2_2") (pintype "passive"))
      (node (ref "C7") (pin "2") (pinfunction "2_2") (pintype "passive"))
      (node (ref "C8") (pin "-") (pinfunction "-_-") (pintype "passive"))
      (node (ref "C9") (pin "2") (pinfunction "2_2") (pintype "passive"))
      (node (ref "CLEAR") (pin "1") (pinfunction "O_1") (pintype "passive"))
      (node (ref "CONT") (pin "1") (pinfunction "O_1") (pintype "passive"))
      (node (ref "D2") (pin "A") (pinfunction "A_A") (pintype "passive"))
      (node (ref "DEP") (pin "3") (pinfunction "S_3") (pintype "passive"))
      (node (ref "EXAM") (pin "1") (pinfunction "O_1") (pintype "passive"))
      (node (ref "HALT") (pin "2") (pinfunction "P_2") (pintype "passive"))
      (node (ref "IC1") (pin "2") (pinfunction "GND_2") (pintype "passive"))
      (node (ref "J1") (pin "17") (pinfunction "1_17") (pintype "passive"))
      (node (ref "J1") (pin "18") (pinfunction "1_18") (pintype "passive"))
      (node (ref "J1") (pin "49") (pinfunction "1_49") (pintype "passive"))
      (node (ref "J2") (pin "17") (pinfunction "1_17") (pintype "passive"))
      (node (ref "J2") (pin "18") (pinfunction "1_18") (pintype "passive"))
      (node (ref "J2") (pin "49") (pinfunction "1_49") (pintype "passive"))
      (node (ref "J3") (pin "2") (pinfunction "2_2") (pintype "passive"))
      (node (ref "J3") (pin "3") (pinfunction "3_3") (pintype "passive"))
      (node (ref "LA") (pin "1") (pinfunction "O_1") (pintype "passive"))
      (node (ref "LXA") (pin "1") (pinfunction "O_1") (pintype "passive"))
      (node (ref "PLOCK") (pin "1") (pinfunction "O_1") (pintype "passive"))
      (node (ref "ROTSW") (pin "A") (pinfunction "A_A") (pintype "passive"))
      (node (ref "ROTSW") (pin "B") (pinfunction "B_B") (pintype "passive"))
      (node (ref "ROTSW") (pin "C") (pinfunction "C_C") (pintype "passive"))
      (node (ref "RP1") (pin "1") (pinfunction "1_1") (pintype "passive"))
      (node (ref "RP2") (pin "1") (pinfunction "1_1") (pintype "passive"))
      (node (ref "RP3") (pin "1") (pinfunction "1_1") (pintype "passive"))
      (node (ref "RP4") (pin "1") (pinfunction "1_1") (pintype "passive"))
      (node (ref "SR0") (pin "2") (pinfunction "P_2") (pintype "passive"))
      (node (ref "SR1") (pin "2") (pinfunction "P_2") (pintype "passive"))
      (node (ref "SR10") (pin "2") (pinfunction "P_2") (pintype "passive"))
      (node (ref "SR11") (pin "2") (pinfunction "P_2") (pintype "passive"))
      (node (ref "SR2") (pin "2") (pinfunction "P_2") (pintype "passive"))
      (node (ref "SR3") (pin "2") (pinfunction "P_2") (pintype "passive"))
      (node (ref "SR4") (pin "2") (pinfunction "P_2") (pintype "passive"))
      (node (ref "SR5") (pin "2") (pinfunction "P_2") (pintype "passive"))
      (node (ref "SR6") (pin "2") (pinfunction "P_2") (pintype "passive"))
      (node (ref "SR7") (pin "2") (pinfunction "P_2") (pintype "passive"))
      (node (ref "SR8") (pin "2") (pinfunction "P_2") (pintype "passive"))
      (node (ref "SR9") (pin "2") (pinfunction "P_2") (pintype "passive"))
      (node (ref "TP2") (pin "TP") (pinfunction "TP_TP") (pintype "input"))
      (node (ref "U1") (pin "1") (pinfunction "OC_1") (pintype "input"))
      (node (ref "U2") (pin "1") (pinfunction "OC_1") (pintype "input"))
      (node (ref "U2") (pin "18") (pinfunction "8D_18") (pintype "input"))
      (node (ref "U8") (pin "1") (pinfunction "GND_1") (pintype "power_in"))
    )
    (net (code "25") (name "HALT_SW") (class "Default")
      (node (ref "HALT") (pin "1") (pinfunction "O_1") (pintype "passive"))
      (node (ref "RP7") (pin "10") (pinfunction "10_10") (pintype "passive"))
      (node (ref "U10") (pin "4") (pinfunction "A2_4") (pintype "input"))
      (node (ref "U11") (pin "11") (pinfunction "CLK_11") (pintype "input"))
      (node (ref "U12") (pin "11") (pinfunction "I_11") (pintype "input"))
      (node (ref "U12") (pin "12") (pinfunction "O_12") (pintype "open_collector"))
    )
    (net (code "26") (name "HALT_SW_REQ") (class "Default")
      (node (ref "U11") (pin "9") (pinfunction "Q_9") (pintype "output"))
      (node (ref "U7") (pin "11") (pinfunction "I9_11") (pintype "input"))
    )
    (net (code "27") (name "LOAD_DAR") (class "Default")
      (node (ref "J1") (pin "15") (pinfunction "1_15") (pintype "passive"))
      (node (ref "J2") (pin "15") (pinfunction "1_15") (pintype "passive"))
    )
    (net (code "28") (name "MA0") (class "Default")
      (node (ref "J1") (pin "30") (pinfunction "1_30") (pintype "passive"))
      (node (ref "J2") (pin "30") (pinfunction "1_30") (pintype "passive"))
      (node (ref "U1") (pin "8") (pinfunction "4D_8") (pintype "input"))
    )
    (net (code "29") (name "MA1") (class "Default")
      (node (ref "J1") (pin "32") (pinfunction "1_32") (pintype "passive"))
      (node (ref "J2") (pin "32") (pinfunction "1_32") (pintype "passive"))
      (node (ref "U1") (pin "13") (pinfunction "5D_13") (pintype "input"))
    )
    (net (code "30") (name "MA2") (class "Default")
      (node (ref "J1") (pin "28") (pinfunction "1_28") (pintype "passive"))
      (node (ref "J2") (pin "28") (pinfunction "1_28") (pintype "passive"))
      (node (ref "U1") (pin "14") (pinfunction "6D_14") (pintype "input"))
    )
    (net (code "31") (name "MA3") (class "Default")
      (node (ref "J1") (pin "26") (pinfunction "1_26") (pintype "passive"))
      (node (ref "J2") (pin "26") (pinfunction "1_26") (pintype "passive"))
      (node (ref "U1") (pin "17") (pinfunction "7D_17") (pintype "input"))
      (node (ref "U13") (pin "9") (pinfunction "I7_9") (pintype "input"))
    )
    (net (code "32") (name "MA4") (class "Default")
      (node (ref "J1") (pin "23") (pinfunction "1_23") (pintype "passive"))
      (node (ref "J2") (pin "23") (pinfunction "1_23") (pintype "passive"))
      (node (ref "U1") (pin "18") (pinfunction "8D_18") (pintype "input"))
      (node (ref "U13") (pin "8") (pinfunction "I6_8") (pintype "input"))
    )
    (net (code "33") (name "MA5") (class "Default")
      (node (ref "J1") (pin "25") (pinfunction "1_25") (pintype "passive"))
      (node (ref "J2") (pin "25") (pinfunction "1_25") (pintype "passive"))
      (node (ref "U13") (pin "7") (pinfunction "I5_7") (pintype "input"))
      (node (ref "U2") (pin "3") (pinfunction "1D_3") (pintype "input"))
    )
    (net (code "34") (name "MA6") (class "Default")
      (node (ref "J1") (pin "27") (pinfunction "1_27") (pintype "passive"))
      (node (ref "J2") (pin "27") (pinfunction "1_27") (pintype "passive"))
      (node (ref "U13") (pin "6") (pinfunction "I4_6") (pintype "input"))
      (node (ref "U2") (pin "4") (pinfunction "2D_4") (pintype "input"))
    )
    (net (code "35") (name "MA7") (class "Default")
      (node (ref "J1") (pin "29") (pinfunction "1_29") (pintype "passive"))
      (node (ref "J2") (pin "29") (pinfunction "1_29") (pintype "passive"))
      (node (ref "U13") (pin "5") (pinfunction "I3_5") (pintype "input"))
      (node (ref "U2") (pin "7") (pinfunction "3D_7") (pintype "input"))
    )
    (net (code "36") (name "MA8") (class "Default")
      (node (ref "J1") (pin "31") (pinfunction "1_31") (pintype "passive"))
      (node (ref "J2") (pin "31") (pinfunction "1_31") (pintype "passive"))
      (node (ref "U13") (pin "4") (pinfunction "I2_4") (pintype "input"))
      (node (ref "U2") (pin "8") (pinfunction "4D_8") (pintype "input"))
    )
    (net (code "37") (name "MA9") (class "Default")
      (node (ref "J1") (pin "33") (pinfunction "1_33") (pintype "passive"))
      (node (ref "J2") (pin "33") (pinfunction "1_33") (pintype "passive"))
      (node (ref "U13") (pin "3") (pinfunction "I1_3") (pintype "input"))
      (node (ref "U2") (pin "13") (pinfunction "5D_13") (pintype "input"))
      (node (ref "U7") (pin "6") (pinfunction "I4_6") (pintype "input"))
    )
    (net (code "38") (name "MA10") (class "Default")
      (node (ref "J1") (pin "37") (pinfunction "1_37") (pintype "passive"))
      (node (ref "J2") (pin "37") (pinfunction "1_37") (pintype "passive"))
      (node (ref "U13") (pin "2") (pinfunction "I0_2") (pintype "input"))
      (node (ref "U2") (pin "14") (pinfunction "6D_14") (pintype "input"))
      (node (ref "U7") (pin "5") (pinfunction "I3_5") (pintype "input"))
    )
    (net (code "39") (name "MA11") (class "Default")
      (node (ref "J1") (pin "39") (pinfunction "1_39") (pintype "passive"))
      (node (ref "J2") (pin "39") (pinfunction "1_39") (pintype "passive"))
      (node (ref "U13") (pin "11") (pinfunction "OE/I8_11") (pintype "input"))
      (node (ref "U2") (pin "17") (pinfunction "7D_17") (pintype "input"))
      (node (ref "U7") (pin "4") (pinfunction "I2_4") (pintype "input"))
    )
    (net (code "40") (name "Net-(EMA0-C)") (class "Default")
      (node (ref "EMA0") (pin "K") (pinfunction "C_K") (pintype "passive"))
      (node (ref "RP1") (pin "3") (pinfunction "3_3") (pintype "passive"))
    )
    (net (code "41") (name "Net-(EMA1-C)") (class "Default")
      (node (ref "EMA1") (pin "K") (pinfunction "C_K") (pintype "passive"))
      (node (ref "RP1") (pin "4") (pinfunction "4_4") (pintype "passive"))
    )
    (net (code "42") (name "Net-(EMA2-C)") (class "Default")
      (node (ref "EMA2") (pin "K") (pinfunction "C_K") (pintype "passive"))
      (node (ref "RP1") (pin "5") (pinfunction "5_5") (pintype "passive"))
    )
    (net (code "43") (name "Net-(F1-Pad1)") (class "Default")
      (node (ref "F1") (pin "1") (pinfunction "1_1") (pintype "passive"))
      (node (ref "J3") (pin "1") (pinfunction "1_1") (pintype "passive"))
    )
    (net (code "44") (name "Net-(IC1-VI)") (class "Default")
      (node (ref "C7") (pin "1") (pinfunction "1_1") (pintype "passive"))
      (node (ref "D1") (pin "C") (pinfunction "C_C") (pintype "passive"))
      (node (ref "IC1") (pin "1") (pinfunction "VI_1") (pintype "input"))
    )
    (net (code "45") (name "Net-(J5-Pad2)") (class "Default")
      (node (ref "J5") (pin "2") (pinfunction "2_2") (pintype "passive"))
      (node (ref "JP2") (pin "1") (pinfunction "1_1") (pintype "passive"))
    )
    (net (code "46") (name "Net-(MA0-C)") (class "Default")
      (node (ref "MA0") (pin "K") (pinfunction "C_K") (pintype "passive"))
      (node (ref "RP1") (pin "6") (pinfunction "6_6") (pintype "passive"))
    )
    (net (code "47") (name "Net-(MA1-C)") (class "Default")
      (node (ref "MA1") (pin "K") (pinfunction "C_K") (pintype "passive"))
      (node (ref "RP1") (pin "7") (pinfunction "7_7") (pintype "passive"))
    )
    (net (code "48") (name "Net-(MA2-C)") (class "Default")
      (node (ref "MA2") (pin "K") (pinfunction "C_K") (pintype "passive"))
      (node (ref "RP1") (pin "8") (pinfunction "8_8") (pintype "passive"))
    )
    (net (code "49") (name "Net-(MA3-C)") (class "Default")
      (node (ref "MA3") (pin "K") (pinfunction "C_K") (pintype "passive"))
      (node (ref "RP1") (pin "9") (pinfunction "9_9") (pintype "passive"))
    )
    (net (code "50") (name "Net-(MA4-C)") (class "Default")
      (node (ref "MA4") (pin "K") (pinfunction "C_K") (pintype "passive"))
      (node (ref "RP1") (pin "10") (pinfunction "10_10") (pintype "passive"))
    )
    (net (code "51") (name "Net-(MA5-C)") (class "Default")
      (node (ref "MA5") (pin "K") (pinfunction "C_K") (pintype "passive"))
      (node (ref "RP2") (pin "2") (pinfunction "2_2") (pintype "passive"))
    )
    (net (code "52") (name "Net-(MA6-C)") (class "Default")
      (node (ref "MA6") (pin "K") (pinfunction "C_K") (pintype "passive"))
      (node (ref "RP2") (pin "3") (pinfunction "3_3") (pintype "passive"))
    )
    (net (code "53") (name "Net-(MA7-C)") (class "Default")
      (node (ref "MA7") (pin "K") (pinfunction "C_K") (pintype "passive"))
      (node (ref "RP2") (pin "4") (pinfunction "4_4") (pintype "passive"))
    )
    (net (code "54") (name "Net-(MA8-C)") (class "Default")
      (node (ref "MA8") (pin "K") (pinfunction "C_K") (pintype "passive"))
      (node (ref "RP2") (pin "5") (pinfunction "5_5") (pintype "passive"))
    )
    (net (code "55") (name "Net-(MA9-C)") (class "Default")
      (node (ref "MA9") (pin "K") (pinfunction "C_K") (pintype "passive"))
      (node (ref "RP2") (pin "6") (pinfunction "6_6") (pintype "passive"))
    )
    (net (code "56") (name "Net-(MA10-C)") (class "Default")
      (node (ref "MA10") (pin "K") (pinfunction "C_K") (pintype "passive"))
      (node (ref "RP2") (pin "7") (pinfunction "7_7") (pintype "passive"))
    )
    (net (code "57") (name "Net-(MA11-C)") (class "Default")
      (node (ref "MA11") (pin "K") (pinfunction "C_K") (pintype "passive"))
      (node (ref "RP2") (pin "8") (pinfunction "8_8") (pintype "passive"))
    )
    (net (code "58") (name "Net-(MD0-C)") (class "Default")
      (node (ref "MD0") (pin "K") (pinfunction "C_K") (pintype "passive"))
      (node (ref "RP3") (pin "2") (pinfunction "2_2") (pintype "passive"))
    )
    (net (code "59") (name "Net-(MD1-C)") (class "Default")
      (node (ref "MD1") (pin "K") (pinfunction "C_K") (pintype "passive"))
      (node (ref "RP3") (pin "3") (pinfunction "3_3") (pintype "passive"))
    )
    (net (code "60") (name "Net-(MD2-C)") (class "Default")
      (node (ref "MD2") (pin "K") (pinfunction "C_K") (pintype "passive"))
      (node (ref "RP3") (pin "4") (pinfunction "4_4") (pintype "passive"))
    )
    (net (code "61") (name "Net-(MD3-C)") (class "Default")
      (node (ref "MD3") (pin "K") (pinfunction "C_K") (pintype "passive"))
      (node (ref "RP3") (pin "5") (pinfunction "5_5") (pintype "passive"))
    )
    (net (code "62") (name "Net-(MD4-C)") (class "Default")
      (node (ref "MD4") (pin "K") (pinfunction "C_K") (pintype "passive"))
      (node (ref "RP3") (pin "6") (pinfunction "6_6") (pintype "passive"))
    )
    (net (code "63") (name "Net-(MD5-C)") (class "Default")
      (node (ref "MD5") (pin "K") (pinfunction "C_K") (pintype "passive"))
      (node (ref "RP3") (pin "7") (pinfunction "7_7") (pintype "passive"))
    )
    (net (code "64") (name "Net-(MD6-C)") (class "Default")
      (node (ref "MD6") (pin "K") (pinfunction "C_K") (pintype "passive"))
      (node (ref "RP4") (pin "2") (pinfunction "2_2") (pintype "passive"))
    )
    (net (code "65") (name "Net-(MD7-C)") (class "Default")
      (node (ref "MD7") (pin "K") (pinfunction "C_K") (pintype "passive"))
      (node (ref "RP4") (pin "3") (pinfunction "3_3") (pintype "passive"))
    )
    (net (code "66") (name "Net-(MD8-C)") (class "Default")
      (node (ref "MD8") (pin "K") (pinfunction "C_K") (pintype "passive"))
      (node (ref "RP4") (pin "4") (pinfunction "4_4") (pintype "passive"))
    )
    (net (code "67") (name "Net-(MD9-C)") (class "Default")
      (node (ref "MD9") (pin "K") (pinfunction "C_K") (pintype "passive"))
      (node (ref "RP4") (pin "5") (pinfunction "5_5") (pintype "passive"))
    )
    (net (code "68") (name "Net-(MD10-C)") (class "Default")
      (node (ref "MD10") (pin "K") (pinfunction "C_K") (pintype "passive"))
      (node (ref "RP4") (pin "6") (pinfunction "6_6") (pintype "passive"))
    )
    (net (code "69") (name "Net-(MD11-C)") (class "Default")
      (node (ref "MD11") (pin "K") (pinfunction "C_K") (pintype "passive"))
      (node (ref "RP4") (pin "7") (pinfunction "7_7") (pintype "passive"))
    )
    (net (code "70") (name "Net-(S1-P)") (class "Default")
      (node (ref "F1") (pin "2") (pinfunction "2_2") (pintype "passive"))
      (node (ref "S1") (pin "2") (pinfunction "P_2") (pintype "passive"))
    )
    (net (code "71") (name "Net-(S1-S)") (class "Default")
      (node (ref "D1") (pin "A") (pinfunction "A_A") (pintype "passive"))
      (node (ref "S1") (pin "3") (pinfunction "S_3") (pintype "passive"))
    )
    (net (code "72") (name "Net-(SR0A-S)") (class "Default")
      (node (ref "RP6") (pin "3") (pinfunction "3_3") (pintype "passive"))
      (node (ref "SR0") (pin "3") (pinfunction "S_3") (pintype "passive"))
      (node (ref "U5") (pin "2") (pinfunction "A1_2") (pintype "input"))
    )
    (net (code "73") (name "Net-(SR1A-S)") (class "Default")
      (node (ref "RP6") (pin "4") (pinfunction "4_4") (pintype "passive"))
      (node (ref "SR1") (pin "3") (pinfunction "S_3") (pintype "passive"))
      (node (ref "U5") (pin "4") (pinfunction "A2_4") (pintype "input"))
    )
    (net (code "74") (name "Net-(SR2A-S)") (class "Default")
      (node (ref "RP6") (pin "5") (pinfunction "5_5") (pintype "passive"))
      (node (ref "SR2") (pin "3") (pinfunction "S_3") (pintype "passive"))
      (node (ref "U5") (pin "6") (pinfunction "A3_6") (pintype "input"))
    )
    (net (code "75") (name "Net-(SR3A-S)") (class "Default")
      (node (ref "RP6") (pin "6") (pinfunction "6_6") (pintype "passive"))
      (node (ref "SR3") (pin "3") (pinfunction "S_3") (pintype "passive"))
      (node (ref "U5") (pin "10") (pinfunction "A4_10") (pintype "input"))
    )
    (net (code "76") (name "Net-(SR4A-S)") (class "Default")
      (node (ref "RP6") (pin "7") (pinfunction "7_7") (pintype "passive"))
      (node (ref "SR4") (pin "3") (pinfunction "S_3") (pintype "passive"))
      (node (ref "U5") (pin "12") (pinfunction "A5_12") (pintype "input"))
    )
    (net (code "77") (name "Net-(SR5A-S)") (class "Default")
      (node (ref "RP6") (pin "8") (pinfunction "8_8") (pintype "passive"))
      (node (ref "SR5") (pin "3") (pinfunction "S_3") (pintype "passive"))
      (node (ref "U5") (pin "14") (pinfunction "A6_14") (pintype "input"))
    )
    (net (code "78") (name "Net-(SR6A-S)") (class "Default")
      (node (ref "RP5") (pin "3") (pinfunction "3_3") (pintype "passive"))
      (node (ref "SR6") (pin "3") (pinfunction "S_3") (pintype "passive"))
      (node (ref "U6") (pin "2") (pinfunction "A1_2") (pintype "input"))
    )
    (net (code "79") (name "Net-(SR7A-S)") (class "Default")
      (node (ref "RP5") (pin "4") (pinfunction "4_4") (pintype "passive"))
      (node (ref "SR7") (pin "3") (pinfunction "S_3") (pintype "passive"))
      (node (ref "U6") (pin "4") (pinfunction "A2_4") (pintype "input"))
    )
    (net (code "80") (name "Net-(SR8A-S)") (class "Default")
      (node (ref "RP5") (pin "5") (pinfunction "5_5") (pintype "passive"))
      (node (ref "SR8") (pin "3") (pinfunction "S_3") (pintype "passive"))
      (node (ref "U6") (pin "6") (pinfunction "A3_6") (pintype "input"))
    )
    (net (code "81") (name "Net-(SR9A-S)") (class "Default")
      (node (ref "RP5") (pin "6") (pinfunction "6_6") (pintype "passive"))
      (node (ref "SR9") (pin "3") (pinfunction "S_3") (pintype "passive"))
      (node (ref "U6") (pin "10") (pinfunction "A4_10") (pintype "input"))
    )
    (net (code "82") (name "Net-(SR10A-S)") (class "Default")
      (node (ref "RP5") (pin "7") (pinfunction "7_7") (pintype "passive"))
      (node (ref "SR10") (pin "3") (pinfunction "S_3") (pintype "passive"))
    )
    (net (code "83") (name "Net-(SR11A-S)") (class "Default")
      (node (ref "RP5") (pin "8") (pinfunction "8_8") (pintype "passive"))
      (node (ref "SR11") (pin "3") (pinfunction "S_3") (pintype "passive"))
      (node (ref "U6") (pin "12") (pinfunction "A5_12") (pintype "input"))
      (node (ref "U6") (pin "14") (pinfunction "A6_14") (pintype "input"))
    )
    (net (code "84") (name "Net-(U1A-1Q)") (class "Default")
      (node (ref "EMA0") (pin "A") (pinfunction "A_A") (pintype "passive"))
      (node (ref "U1") (pin "2") (pinfunction "1Q_2") (pintype "tri_state"))
    )
    (net (code "85") (name "Net-(U1A-2Q)") (class "Default")
      (node (ref "EMA1") (pin "A") (pinfunction "A_A") (pintype "passive"))
      (node (ref "U1") (pin "5") (pinfunction "2Q_5") (pintype "tri_state"))
    )
    (net (code "86") (name "Net-(U1A-3Q)") (class "Default")
      (node (ref "EMA2") (pin "A") (pinfunction "A_A") (pintype "passive"))
      (node (ref "U1") (pin "6") (pinfunction "3Q_6") (pintype "tri_state"))
    )
    (net (code "87") (name "Net-(U1A-4Q)") (class "Default")
      (node (ref "MA0") (pin "A") (pinfunction "A_A") (pintype "passive"))
      (node (ref "U1") (pin "9") (pinfunction "4Q_9") (pintype "tri_state"))
    )
    (net (code "88") (name "Net-(U1A-5Q)") (class "Default")
      (node (ref "MA1") (pin "A") (pinfunction "A_A") (pintype "passive"))
      (node (ref "U1") (pin "12") (pinfunction "5Q_12") (pintype "tri_state"))
    )
    (net (code "89") (name "Net-(U1A-6Q)") (class "Default")
      (node (ref "MA2") (pin "A") (pinfunction "A_A") (pintype "passive"))
      (node (ref "U1") (pin "15") (pinfunction "6Q_15") (pintype "tri_state"))
    )
    (net (code "90") (name "Net-(U1A-7Q)") (class "Default")
      (node (ref "MA3") (pin "A") (pinfunction "A_A") (pintype "passive"))
      (node (ref "U1") (pin "16") (pinfunction "7Q_16") (pintype "tri_state"))
    )
    (net (code "91") (name "Net-(U1A-8Q)") (class "Default")
      (node (ref "MA4") (pin "A") (pinfunction "A_A") (pintype "passive"))
      (node (ref "U1") (pin "19") (pinfunction "8Q_19") (pintype "tri_state"))
    )
    (net (code "92") (name "Net-(U2A-1Q)") (class "Default")
      (node (ref "MA5") (pin "A") (pinfunction "A_A") (pintype "passive"))
      (node (ref "U2") (pin "2") (pinfunction "1Q_2") (pintype "tri_state"))
    )
    (net (code "93") (name "Net-(U2A-2Q)") (class "Default")
      (node (ref "MA6") (pin "A") (pinfunction "A_A") (pintype "passive"))
      (node (ref "U2") (pin "5") (pinfunction "2Q_5") (pintype "tri_state"))
    )
    (net (code "94") (name "Net-(U2A-3Q)") (class "Default")
      (node (ref "MA7") (pin "A") (pinfunction "A_A") (pintype "passive"))
      (node (ref "U2") (pin "6") (pinfunction "3Q_6") (pintype "tri_state"))
    )
    (net (code "95") (name "Net-(U2A-4Q)") (class "Default")
      (node (ref "MA8") (pin "A") (pinfunction "A_A") (pintype "passive"))
      (node (ref "U2") (pin "9") (pinfunction "4Q_9") (pintype "tri_state"))
    )
    (net (code "96") (name "Net-(U2A-5Q)") (class "Default")
      (node (ref "MA9") (pin "A") (pinfunction "A_A") (pintype "passive"))
      (node (ref "U2") (pin "12") (pinfunction "5Q_12") (pintype "tri_state"))
    )
    (net (code "97") (name "Net-(U2A-6Q)") (class "Default")
      (node (ref "MA10") (pin "A") (pinfunction "A_A") (pintype "passive"))
      (node (ref "U2") (pin "15") (pinfunction "6Q_15") (pintype "tri_state"))
    )
    (net (code "98") (name "Net-(U2A-7Q)") (class "Default")
      (node (ref "MA11") (pin "A") (pinfunction "A_A") (pintype "passive"))
      (node (ref "U2") (pin "16") (pinfunction "7Q_16") (pintype "tri_state"))
    )
    (net (code "99") (name "Net-(U3A-Q1)") (class "Default")
      (node (ref "MD0") (pin "A") (pinfunction "A_A") (pintype "passive"))
      (node (ref "U3") (pin "2") (pinfunction "Q1_2") (pintype "output"))
    )
    (net (code "100") (name "Net-(U3A-Q2)") (class "Default")
      (node (ref "MD1") (pin "A") (pinfunction "A_A") (pintype "passive"))
      (node (ref "U3") (pin "5") (pinfunction "Q2_5") (pintype "output"))
    )
    (net (code "101") (name "Net-(U3A-Q3)") (class "Default")
      (node (ref "MD2") (pin "A") (pinfunction "A_A") (pintype "passive"))
      (node (ref "U3") (pin "7") (pinfunction "Q3_7") (pintype "output"))
    )
    (net (code "102") (name "Net-(U3A-Q4)") (class "Default")
      (node (ref "MD3") (pin "A") (pinfunction "A_A") (pintype "passive"))
      (node (ref "U3") (pin "10") (pinfunction "Q4_10") (pintype "output"))
    )
    (net (code "103") (name "Net-(U3A-Q5)") (class "Default")
      (node (ref "MD4") (pin "A") (pinfunction "A_A") (pintype "passive"))
      (node (ref "U3") (pin "12") (pinfunction "Q5_12") (pintype "output"))
    )
    (net (code "104") (name "Net-(U3A-Q6)") (class "Default")
      (node (ref "MD5") (pin "A") (pinfunction "A_A") (pintype "passive"))
      (node (ref "U3") (pin "15") (pinfunction "Q6_15") (pintype "output"))
    )
    (net (code "105") (name "Net-(U4A-Q1)") (class "Default")
      (node (ref "MD6") (pin "A") (pinfunction "A_A") (pintype "passive"))
      (node (ref "U4") (pin "2") (pinfunction "Q1_2") (pintype "output"))
    )
    (net (code "106") (name "Net-(U4A-Q2)") (class "Default")
      (node (ref "MD7") (pin "A") (pinfunction "A_A") (pintype "passive"))
      (node (ref "U4") (pin "5") (pinfunction "Q2_5") (pintype "output"))
    )
    (net (code "107") (name "Net-(U4A-Q3)") (class "Default")
      (node (ref "MD8") (pin "A") (pinfunction "A_A") (pintype "passive"))
      (node (ref "U4") (pin "7") (pinfunction "Q3_7") (pintype "output"))
    )
    (net (code "108") (name "Net-(U4A-Q4)") (class "Default")
      (node (ref "MD9") (pin "A") (pinfunction "A_A") (pintype "passive"))
      (node (ref "U4") (pin "10") (pinfunction "Q4_10") (pintype "output"))
    )
    (net (code "109") (name "Net-(U4A-Q5)") (class "Default")
      (node (ref "MD10") (pin "A") (pinfunction "A_A") (pintype "passive"))
      (node (ref "U4") (pin "12") (pinfunction "Q5_12") (pintype "output"))
    )
    (net (code "110") (name "Net-(U4A-Q6)") (class "Default")
      (node (ref "MD11") (pin "A") (pinfunction "A_A") (pintype "passive"))
      (node (ref "U4") (pin "15") (pinfunction "Q6_15") (pintype "output"))
    )
    (net (code "111") (name "Net-(U8-CV)") (class "Default")
      (node (ref "C2") (pin "1") (pinfunction "1_1") (pintype "passive"))
      (node (ref "U8") (pin "5") (pinfunction "CV_5") (pintype "passive"))
    )
    (net (code "112") (name "Net-(U8-DISCH)") (class "Default")
      (node (ref "R1") (pin "1") (pinfunction "1_1") (pintype "passive"))
      (node (ref "R2") (pin "2") (pinfunction "2_2") (pintype "passive"))
      (node (ref "U8") (pin "7") (pinfunction "DISCH_7") (pintype "input"))
    )
    (net (code "113") (name "Net-(U8-OUT)") (class "Default")
      (node (ref "JP1") (pin "2") (pinfunction "2_2") (pintype "passive"))
      (node (ref "U8") (pin "3") (pinfunction "OUT_3") (pintype "output"))
    )
    (net (code "114") (name "Net-(U8-TRIG)") (class "Default")
      (node (ref "C1") (pin "+") (pinfunction "+_+") (pintype "passive"))
      (node (ref "R2") (pin "1") (pinfunction "1_1") (pintype "passive"))
      (node (ref "U8") (pin "2") (pinfunction "TRIG_2") (pintype "bidirectional"))
      (node (ref "U8") (pin "6") (pinfunction "TRSH_6") (pintype "input"))
    )
    (net (code "115") (name "Net-(U11A-CLK)") (class "Default")
      (node (ref "JP1") (pin "1") (pinfunction "1_1") (pintype "passive"))
      (node (ref "R3") (pin "1") (pinfunction "1_1") (pintype "passive"))
      (node (ref "U11") (pin "3") (pinfunction "CLK_3") (pintype "input"))
    )
    (net (code "116") (name "PANEL_IOT") (class "Default")
      (node (ref "J1") (pin "20") (pinfunction "1_20") (pintype "passive"))
      (node (ref "J2") (pin "20") (pinfunction "1_20") (pintype "passive"))
      (node (ref "U13") (pin "13") (pinfunction "O1_13") (pintype "bidirectional"))
      (node (ref "U7") (pin "1") (pinfunction "CLK/I0_1") (pintype "input"))
    )
    (net (code "117") (name "RUN_LED") (class "Default")
      (node (ref "RP2") (pin "10") (pinfunction "10_10") (pintype "passive"))
      (node (ref "RUN") (pin "K") (pinfunction "C_K") (pintype "passive"))
    )
    (net (code "118") (name "RUN_LED_H") (class "Default")
      (node (ref "RUN") (pin "A") (pinfunction "A_A") (pintype "passive"))
      (node (ref "U13") (pin "18") (pinfunction "O6_18") (pintype "bidirectional"))
    )
    (net (code "119") (name "SKIP") (class "Default")
      (node (ref "J1") (pin "19") (pinfunction "1_19") (pintype "passive"))
      (node (ref "J2") (pin "19") (pinfunction "1_19") (pintype "passive"))
      (node (ref "U12") (pin "3") (pinfunction "I_3") (pintype "input"))
      (node (ref "U7") (pin "18") (pinfunction "O4_18") (pintype "bidirectional"))
    )
    (net (code "120") (name "VCC") (class "Default")
      (node (ref "C10") (pin "1") (pinfunction "1_1") (pintype "passive"))
      (node (ref "C11") (pin "1") (pinfunction "1_1") (pintype "passive"))
      (node (ref "C12") (pin "1") (pinfunction "1_1") (pintype "passive"))
      (node (ref "C13") (pin "1") (pinfunction "1_1") (pintype "passive"))
      (node (ref "C14") (pin "1") (pinfunction "1_1") (pintype "passive"))
      (node (ref "C15") (pin "1") (pinfunction "1_1") (pintype "passive"))
      (node (ref "C16") (pin "1") (pinfunction "1_1") (pintype "passive"))
      (node (ref "C17") (pin "1") (pinfunction "1_1") (pintype "passive"))
      (node (ref "C18") (pin "1") (pinfunction "1_1") (pintype "passive"))
      (node (ref "C19") (pin "1") (pinfunction "1_1") (pintype "passive"))
      (node (ref "C20") (pin "1") (pinfunction "1_1") (pintype "passive"))
      (node (ref "C21") (pin "1") (pinfunction "1_1") (pintype "passive"))
      (node (ref "C8") (pin "+") (pinfunction "+_+") (pintype "passive"))
      (node (ref "C9") (pin "1") (pinfunction "1_1") (pintype "passive"))
      (node (ref "D2") (pin "C") (pinfunction "C_C") (pintype "passive"))
      (node (ref "FB1") (pin "1") (pinfunction "1_1") (pintype "passive"))
      (node (ref "FB2") (pin "1") (pinfunction "1_1") (pintype "passive"))
      (node (ref "IC1") (pin "3") (pinfunction "VO_3") (pintype "passive"))
      (node (ref "R1") (pin "2") (pinfunction "2_2") (pintype "passive"))
      (node (ref "R3") (pin "2") (pinfunction "2_2") (pintype "passive"))
      (node (ref "R4") (pin "2") (pinfunction "2_2") (pintype "passive"))
      (node (ref "RP5") (pin "1") (pinfunction "1_1") (pintype "passive"))
      (node (ref "RP6") (pin "1") (pinfunction "1_1") (pintype "passive"))
      (node (ref "RP7") (pin "1") (pinfunction "1_1") (pintype "passive"))
      (node (ref "RP8") (pin "1") (pinfunction "1_1") (pintype "passive"))
      (node (ref "TP1") (pin "TP") (pinfunction "TP_TP") (pintype "input"))
      (node (ref "U11") (pin "10") (pinfunction "PRE_10") (pintype "input"))
      (node (ref "U11") (pin "12") (pinfunction "D_12") (pintype "input"))
      (node (ref "U11") (pin "2") (pinfunction "D_2") (pintype "input"))
      (node (ref "U11") (pin "4") (pinfunction "PRE_4") (pintype "input"))
      (node (ref "U3") (pin "1") (pinfunction "CLR_1") (pintype "input"))
      (node (ref "U4") (pin "1") (pinfunction "CLR_1") (pintype "input"))
      (node (ref "U8") (pin "4") (pinfunction "RESET_4") (pintype "input"))
      (node (ref "U8") (pin "8") (pinfunction "V+_8") (pintype "power_in"))
    )
    (net (code "121") (name "unconnected-(BOOTA-S-Pad3)") (class "Default")
      (node (ref "BOOT") (pin "3") (pinfunction "S_3") (pintype "passive"))
    )
    (net (code "122") (name "unconnected-(CLEARA-S-Pad3)") (class "Default")
      (node (ref "CLEAR") (pin "3") (pinfunction "S_3") (pintype "passive"))
    )
    (net (code "123") (name "unconnected-(CONTA-S-Pad3)") (class "Default")
      (node (ref "CONT") (pin "3") (pinfunction "S_3") (pintype "passive"))
    )
    (net (code "124") (name "unconnected-(DEPA-O-Pad1)") (class "Default")
      (node (ref "DEP") (pin "1") (pinfunction "O_1") (pintype "passive"))
    )
    (net (code "125") (name "unconnected-(EXAMA-S-Pad3)") (class "Default")
      (node (ref "EXAM") (pin "3") (pinfunction "S_3") (pintype "passive"))
    )
    (net (code "126") (name "unconnected-(J4-Pad2)") (class "Default")
      (node (ref "J4") (pin "2") (pinfunction "2_2") (pintype "passive"))
    )
    (net (code "127") (name "unconnected-(LAA-S-Pad3)") (class "Default")
      (node (ref "LA") (pin "3") (pinfunction "S_3") (pintype "passive"))
    )
    (net (code "128") (name "unconnected-(LXAA-S-Pad3)") (class "Default")
      (node (ref "LXA") (pin "3") (pinfunction "S_3") (pintype "passive"))
    )
    (net (code "129") (name "unconnected-(PLOCK-PadB)") (class "Default")
      (node (ref "PLOCK") (pin "B") (pinfunction "B_B") (pintype "passive"))
    )
    (net (code "130") (name "unconnected-(PLOCK-PadB1)") (class "Default")
      (node (ref "PLOCK") (pin "B1") (pinfunction "B1_B1") (pintype "passive"))
    )
    (net (code "131") (name "unconnected-(PLOCK-S-Pad3)") (class "Default")
      (node (ref "PLOCK") (pin "3") (pinfunction "S_3") (pintype "passive"))
    )
    (net (code "132") (name "unconnected-(ROTSW-PadB1)") (class "Default")
      (node (ref "ROTSW") (pin "B1") (pinfunction "B1_B1") (pintype "passive"))
    )
    (net (code "133") (name "unconnected-(ROTSW-PadB2)") (class "Default")
      (node (ref "ROTSW") (pin "B2") (pinfunction "B2_B2") (pintype "passive"))
    )
    (net (code "134") (name "unconnected-(ROTSW-PadB3)") (class "Default")
      (node (ref "ROTSW") (pin "B3") (pinfunction "B3_B3") (pintype "passive"))
    )
    (net (code "135") (name "unconnected-(ROTSW-PadB4)") (class "Default")
      (node (ref "ROTSW") (pin "B4") (pinfunction "B4_B4") (pintype "passive"))
    )
    (net (code "136") (name "unconnected-(ROTSW-PadC1)") (class "Default")
      (node (ref "ROTSW") (pin "C1") (pinfunction "C1_C1") (pintype "passive"))
    )
    (net (code "137") (name "unconnected-(ROTSW-PadC2)") (class "Default")
      (node (ref "ROTSW") (pin "C2") (pinfunction "C2_C2") (pintype "passive"))
    )
    (net (code "138") (name "unconnected-(ROTSW-PadC3)") (class "Default")
      (node (ref "ROTSW") (pin "C3") (pinfunction "C3_C3") (pintype "passive"))
    )
    (net (code "139") (name "unconnected-(ROTSW-PadC4)") (class "Default")
      (node (ref "ROTSW") (pin "C4") (pinfunction "C4_C4") (pintype "passive"))
    )
    (net (code "140") (name "unconnected-(RP1-Pad2)") (class "Default")
      (node (ref "RP1") (pin "2") (pinfunction "2_2") (pintype "passive"))
    )
    (net (code "141") (name "unconnected-(RP2-Pad9)") (class "Default")
      (node (ref "RP2") (pin "9") (pinfunction "9_9") (pintype "passive"))
    )
    (net (code "142") (name "unconnected-(RP3-Pad8)") (class "Default")
      (node (ref "RP3") (pin "8") (pinfunction "8_8") (pintype "passive"))
    )
    (net (code "143") (name "unconnected-(RP4-Pad8)") (class "Default")
      (node (ref "RP4") (pin "8") (pinfunction "8_8") (pintype "passive"))
    )
    (net (code "144") (name "unconnected-(RP5-Pad2)") (class "Default")
      (node (ref "RP5") (pin "2") (pinfunction "2_2") (pintype "passive"))
    )
    (net (code "145") (name "unconnected-(RP6-Pad2)") (class "Default")
      (node (ref "RP6") (pin "2") (pinfunction "2_2") (pintype "passive"))
    )
    (net (code "146") (name "unconnected-(S1-O-Pad1)") (class "Default")
      (node (ref "S1") (pin "1") (pinfunction "O_1") (pintype "passive"))
    )
    (net (code "147") (name "unconnected-(S1-PadB)") (class "Default")
      (node (ref "S1") (pin "B") (pinfunction "B_B") (pintype "passive"))
    )
    (net (code "148") (name "unconnected-(S1-PadB1)") (class "Default")
      (node (ref "S1") (pin "B1") (pinfunction "B1_B1") (pintype "passive"))
    )
    (net (code "149") (name "unconnected-(SR0A-O-Pad1)") (class "Default")
      (node (ref "SR0") (pin "1") (pinfunction "O_1") (pintype "passive"))
    )
    (net (code "150") (name "unconnected-(SR1A-O-Pad1)") (class "Default")
      (node (ref "SR1") (pin "1") (pinfunction "O_1") (pintype "passive"))
    )
    (net (code "151") (name "unconnected-(SR2A-O-Pad1)") (class "Default")
      (node (ref "SR2") (pin "1") (pinfunction "O_1") (pintype "passive"))
    )
    (net (code "152") (name "unconnected-(SR3A-O-Pad1)") (class "Default")
      (node (ref "SR3") (pin "1") (pinfunction "O_1") (pintype "passive"))
    )
    (net (code "153") (name "unconnected-(SR4A-O-Pad1)") (class "Default")
      (node (ref "SR4") (pin "1") (pinfunction "O_1") (pintype "passive"))
    )
    (net (code "154") (name "unconnected-(SR5A-O-Pad1)") (class "Default")
      (node (ref "SR5") (pin "1") (pinfunction "O_1") (pintype "passive"))
    )
    (net (code "155") (name "unconnected-(SR6A-O-Pad1)") (class "Default")
      (node (ref "SR6") (pin "1") (pinfunction "O_1") (pintype "passive"))
    )
    (net (code "156") (name "unconnected-(SR7A-O-Pad1)") (class "Default")
      (node (ref "SR7") (pin "1") (pinfunction "O_1") (pintype "passive"))
    )
    (net (code "157") (name "unconnected-(SR8A-O-Pad1)") (class "Default")
      (node (ref "SR8") (pin "1") (pinfunction "O_1") (pintype "passive"))
    )
    (net (code "158") (name "unconnected-(SR9A-O-Pad1)") (class "Default")
      (node (ref "SR9") (pin "1") (pinfunction "O_1") (pintype "passive"))
    )
    (net (code "159") (name "unconnected-(SR10A-O-Pad1)") (class "Default")
      (node (ref "SR10") (pin "1") (pinfunction "O_1") (pintype "passive"))
    )
    (net (code "160") (name "unconnected-(SR11A-O-Pad1)") (class "Default")
      (node (ref "SR11") (pin "1") (pinfunction "O_1") (pintype "passive"))
    )
    (net (code "161") (name "unconnected-(U2A-8Q-Pad19)") (class "Default")
      (node (ref "U2") (pin "19") (pinfunction "8Q_19") (pintype "tri_state"))
    )
    (net (code "162") (name "unconnected-(U7A-O5-Pad19)") (class "Default")
      (node (ref "U7") (pin "19") (pinfunction "O5_19") (pintype "bidirectional"))
    )
    (net (code "163") (name "unconnected-(U11A-~{Q}-Pad6)") (class "Default")
      (node (ref "U11") (pin "6") (pinfunction "~{Q}_6") (pintype "output"))
    )
    (net (code "164") (name "unconnected-(U11B-~{Q}-Pad8)") (class "Default")
      (node (ref "U11") (pin "8") (pinfunction "~{Q}_8") (pintype "output"))
    )
    (net (code "165") (name "unconnected-(U13A-O0-Pad12)") (class "Default")
      (node (ref "U13") (pin "12") (pinfunction "O0_12") (pintype "bidirectional"))
    )
    (net (code "166") (name "unconnected-(U13A-O2-Pad14)") (class "Default")
      (node (ref "U13") (pin "14") (pinfunction "O2_14") (pintype "bidirectional"))
    )
    (net (code "167") (name "unconnected-(U13A-O3-Pad15)") (class "Default")
      (node (ref "U13") (pin "15") (pinfunction "O3_15") (pintype "bidirectional"))
    )
    (net (code "168") (name "unconnected-(U13A-O4-Pad16)") (class "Default")
      (node (ref "U13") (pin "16") (pinfunction "O4_16") (pintype "bidirectional"))
    )
    (net (code "169") (name "unconnected-(U13A-O7-Pad19)") (class "Default")
      (node (ref "U13") (pin "19") (pinfunction "O7_19") (pintype "bidirectional"))
    )
    (net (code "170") (name "~{AC_DISP}") (class "Default")
      (node (ref "ROTSW") (pin "A3") (pinfunction "A3_A3") (pintype "passive"))
      (node (ref "RP8") (pin "3") (pinfunction "3_3") (pintype "passive"))
      (node (ref "U10") (pin "12") (pinfunction "A5_12") (pintype "input"))
    )
    (net (code "171") (name "~{BOOT_SW}") (class "Default")
      (node (ref "BOOT") (pin "2") (pinfunction "P_2") (pintype "passive"))
      (node (ref "RP7") (pin "2") (pinfunction "2_2") (pintype "passive"))
      (node (ref "U9") (pin "2") (pinfunction "A1_2") (pintype "input"))
    )
    (net (code "172") (name "~{BYTE_READ}") (class "Default")
      (node (ref "J1") (pin "6") (pinfunction "1_6") (pintype "passive"))
      (node (ref "J2") (pin "6") (pinfunction "1_6") (pintype "passive"))
    )
    (net (code "173") (name "~{C0}") (class "Default")
      (node (ref "J1") (pin "7") (pinfunction "1_7") (pintype "passive"))
      (node (ref "J2") (pin "7") (pinfunction "1_7") (pintype "passive"))
      (node (ref "U12") (pin "8") (pinfunction "O_8") (pintype "open_collector"))
    )
    (net (code "174") (name "~{C1}") (class "Default")
      (node (ref "J1") (pin "8") (pinfunction "1_8") (pintype "passive"))
      (node (ref "J2") (pin "8") (pinfunction "1_8") (pintype "passive"))
      (node (ref "U12") (pin "6") (pinfunction "O_6") (pintype "open_collector"))
    )
    (net (code "175") (name "~{CLEAR_SW}") (class "Default")
      (node (ref "CLEAR") (pin "2") (pinfunction "P_2") (pintype "passive"))
      (node (ref "RP7") (pin "5") (pinfunction "5_5") (pintype "passive"))
      (node (ref "U9") (pin "10") (pinfunction "A4_10") (pintype "input"))
    )
    (net (code "176") (name "~{CLR_PANEL_REQ}") (class "Default")
      (node (ref "U11") (pin "1") (pinfunction "CLR_1") (pintype "input"))
      (node (ref "U11") (pin "13") (pinfunction "CLR_13") (pintype "input"))
      (node (ref "U7") (pin "14") (pinfunction "O0_14") (pintype "bidirectional"))
    )
    (net (code "177") (name "~{CONSOLE_BRK_REQ}") (class "Default")
      (node (ref "JP2") (pin "2") (pinfunction "2_2") (pintype "passive"))
      (node (ref "R4") (pin "1") (pinfunction "1_1") (pintype "passive"))
      (node (ref "U7") (pin "20") (pinfunction "O6_20") (pintype "bidirectional"))
    )
    (net (code "178") (name "~{CONT_SW}") (class "Default")
      (node (ref "CONT") (pin "2") (pinfunction "P_2") (pintype "passive"))
      (node (ref "RP7") (pin "6") (pinfunction "6_6") (pintype "passive"))
      (node (ref "U9") (pin "12") (pinfunction "A5_12") (pintype "input"))
    )
    (net (code "179") (name "~{CPREQ}") (class "Default")
      (node (ref "J4") (pin "1") (pinfunction "1_1") (pintype "passive"))
      (node (ref "J5") (pin "1") (pinfunction "1_1") (pintype "passive"))
      (node (ref "U12") (pin "2") (pinfunction "O_2") (pintype "open_collector"))
    )
    (net (code "180") (name "~{DEP_SW}") (class "Default")
      (node (ref "DEP") (pin "2") (pinfunction "P_2") (pintype "passive"))
      (node (ref "RP7") (pin "8") (pinfunction "8_8") (pintype "passive"))
      (node (ref "U10") (pin "2") (pinfunction "A1_2") (pintype "input"))
    )
    (net (code "181") (name "~{DISK_CE}") (class "Default")
      (node (ref "J1") (pin "16") (pinfunction "1_16") (pintype "passive"))
      (node (ref "J2") (pin "16") (pinfunction "1_16") (pintype "passive"))
    )
    (net (code "182") (name "~{EXAM_SW}") (class "Default")
      (node (ref "EXAM") (pin "2") (pinfunction "P_2") (pintype "passive"))
      (node (ref "RP7") (pin "7") (pinfunction "7_7") (pintype "passive"))
      (node (ref "U9") (pin "14") (pinfunction "A6_14") (pintype "input"))
    )
    (net (code "183") (name "~{HALT_SW}") (class "Default")
      (node (ref "HALT") (pin "3") (pinfunction "S_3") (pintype "passive"))
      (node (ref "RP7") (pin "9") (pinfunction "9_9") (pintype "passive"))
      (node (ref "U12") (pin "10") (pinfunction "O_10") (pintype "open_collector"))
      (node (ref "U12") (pin "13") (pinfunction "I_13") (pintype "input"))
    )
    (net (code "184") (name "~{INTGNT}") (class "Default")
      (node (ref "J1") (pin "10") (pinfunction "1_10") (pintype "passive"))
      (node (ref "J2") (pin "10") (pinfunction "1_10") (pintype "passive"))
    )
    (net (code "185") (name "~{INTREQ}") (class "Default")
      (node (ref "J1") (pin "9") (pinfunction "1_9") (pintype "passive"))
      (node (ref "J2") (pin "9") (pinfunction "1_9") (pintype "passive"))
    )
    (net (code "186") (name "~{IOCLR}") (class "Default")
      (node (ref "J1") (pin "12") (pinfunction "1_12") (pintype "passive"))
      (node (ref "J2") (pin "12") (pinfunction "1_12") (pintype "passive"))
    )
    (net (code "187") (name "~{LA_SW}") (class "Default")
      (node (ref "LA") (pin "2") (pinfunction "P_2") (pintype "passive"))
      (node (ref "RP7") (pin "3") (pinfunction "3_3") (pintype "passive"))
      (node (ref "U9") (pin "4") (pinfunction "A2_4") (pintype "input"))
    )
    (net (code "188") (name "~{LXA_SW}") (class "Default")
      (node (ref "LXA") (pin "2") (pinfunction "P_2") (pintype "passive"))
      (node (ref "RP7") (pin "4") (pinfunction "4_4") (pintype "passive"))
      (node (ref "U9") (pin "6") (pinfunction "A3_6") (pintype "input"))
    )
    (net (code "189") (name "~{LXDAR}") (class "Default")
      (node (ref "J1") (pin "14") (pinfunction "1_14") (pintype "passive"))
      (node (ref "J2") (pin "14") (pinfunction "1_14") (pintype "passive"))
      (node (ref "U13") (pin "1") (pinfunction "CLK_1") (pintype "input"))
    )
    (net (code "190") (name "~{LXMAR}") (class "Default")
      (node (ref "J1") (pin "22") (pinfunction "1_22") (pintype "passive"))
      (node (ref "J2") (pin "22") (pinfunction "1_22") (pintype "passive"))
      (node (ref "U7") (pin "9") (pinfunction "I7_9") (pintype "input"))
    )
    (net (code "191") (name "~{MD_DISP}") (class "Default")
      (node (ref "ROTSW") (pin "A1") (pinfunction "A1_A1") (pintype "passive"))
      (node (ref "RP8") (pin "5") (pinfunction "5_5") (pintype "passive"))
      (node (ref "U10") (pin "6") (pinfunction "A3_6") (pintype "input"))
      (node (ref "U7") (pin "2") (pinfunction "I0_2") (pintype "input"))
    )
    (net (code "192") (name "~{MQ_DISP}") (class "Default")
      (node (ref "ROTSW") (pin "A2") (pinfunction "A2_A2") (pintype "passive"))
      (node (ref "RP8") (pin "4") (pinfunction "4_4") (pintype "passive"))
      (node (ref "U10") (pin "10") (pinfunction "A4_10") (pintype "input"))
    )
    (net (code "193") (name "~{PANEL_LOCK}") (class "Default")
      (node (ref "PLOCK") (pin "2") (pinfunction "P_2") (pintype "passive"))
      (node (ref "RP8") (pin "6") (pinfunction "6_6") (pintype "passive"))
      (node (ref "U7") (pin "3") (pinfunction "I1_3") (pintype "input"))
    )
    (net (code "194") (name "~{RD_FN_SW}") (class "Default")
      (node (ref "U10") (pin "1") (pinfunction "G1_1") (pintype "input"))
      (node (ref "U10") (pin "15") (pinfunction "G2_15") (pintype "input"))
      (node (ref "U7") (pin "23") (pinfunction "O9_23") (pintype "bidirectional"))
      (node (ref "U9") (pin "1") (pinfunction "G1_1") (pintype "input"))
      (node (ref "U9") (pin "15") (pinfunction "G2_15") (pintype "input"))
    )
    (net (code "195") (name "~{RD_SR}") (class "Default")
      (node (ref "J1") (pin "3") (pinfunction "1_3") (pintype "passive"))
      (node (ref "J2") (pin "3") (pinfunction "1_3") (pintype "passive"))
      (node (ref "U5") (pin "1") (pinfunction "G1_1") (pintype "input"))
      (node (ref "U5") (pin "15") (pinfunction "G2_15") (pintype "input"))
      (node (ref "U6") (pin "1") (pinfunction "G1_1") (pintype "input"))
      (node (ref "U6") (pin "15") (pinfunction "G2_15") (pintype "input"))
    )
    (net (code "196") (name "~{READ}") (class "Default")
      (node (ref "J1") (pin "11") (pinfunction "1_11") (pintype "passive"))
      (node (ref "J2") (pin "11") (pinfunction "1_11") (pintype "passive"))
      (node (ref "U7") (pin "8") (pinfunction "I6_8") (pintype "input"))
    )
    (net (code "197") (name "~{RUN_LED}") (class "Default")
      (node (ref "U13") (pin "17") (pinfunction "O5_17") (pintype "bidirectional"))
    )
    (net (code "198") (name "~{SKIP}") (class "Default")
      (node (ref "J1") (pin "5") (pinfunction "1_5") (pintype "passive"))
      (node (ref "J2") (pin "5") (pinfunction "1_5") (pintype "passive"))
      (node (ref "U12") (pin "4") (pinfunction "O_4") (pintype "open_collector"))
    )
    (net (code "199") (name "~{STATUS_DISP}") (class "Default")
      (node (ref "ROTSW") (pin "A4") (pinfunction "A4_A4") (pintype "passive"))
      (node (ref "RP8") (pin "2") (pinfunction "2_2") (pintype "passive"))
      (node (ref "U10") (pin "14") (pinfunction "A6_14") (pintype "input"))
    )
    (net (code "200") (name "~{WRITE}") (class "Default")
      (node (ref "J1") (pin "13") (pinfunction "1_13") (pintype "passive"))
      (node (ref "J2") (pin "13") (pinfunction "1_13") (pintype "passive"))
      (node (ref "U7") (pin "7") (pinfunction "I5_7") (pintype "input"))
    )
    (net (code "201") (name "~{WR_SR}") (class "Default")
      (node (ref "J1") (pin "4") (pinfunction "1_4") (pintype "passive"))
      (node (ref "J2") (pin "4") (pinfunction "1_4") (pintype "passive"))
      (node (ref "U7") (pin "10") (pinfunction "I8_10") (pintype "input"))
    )
  )
)
